# SIM7600G.net
KiCad netlist of a schematic drawn in Altium Designer
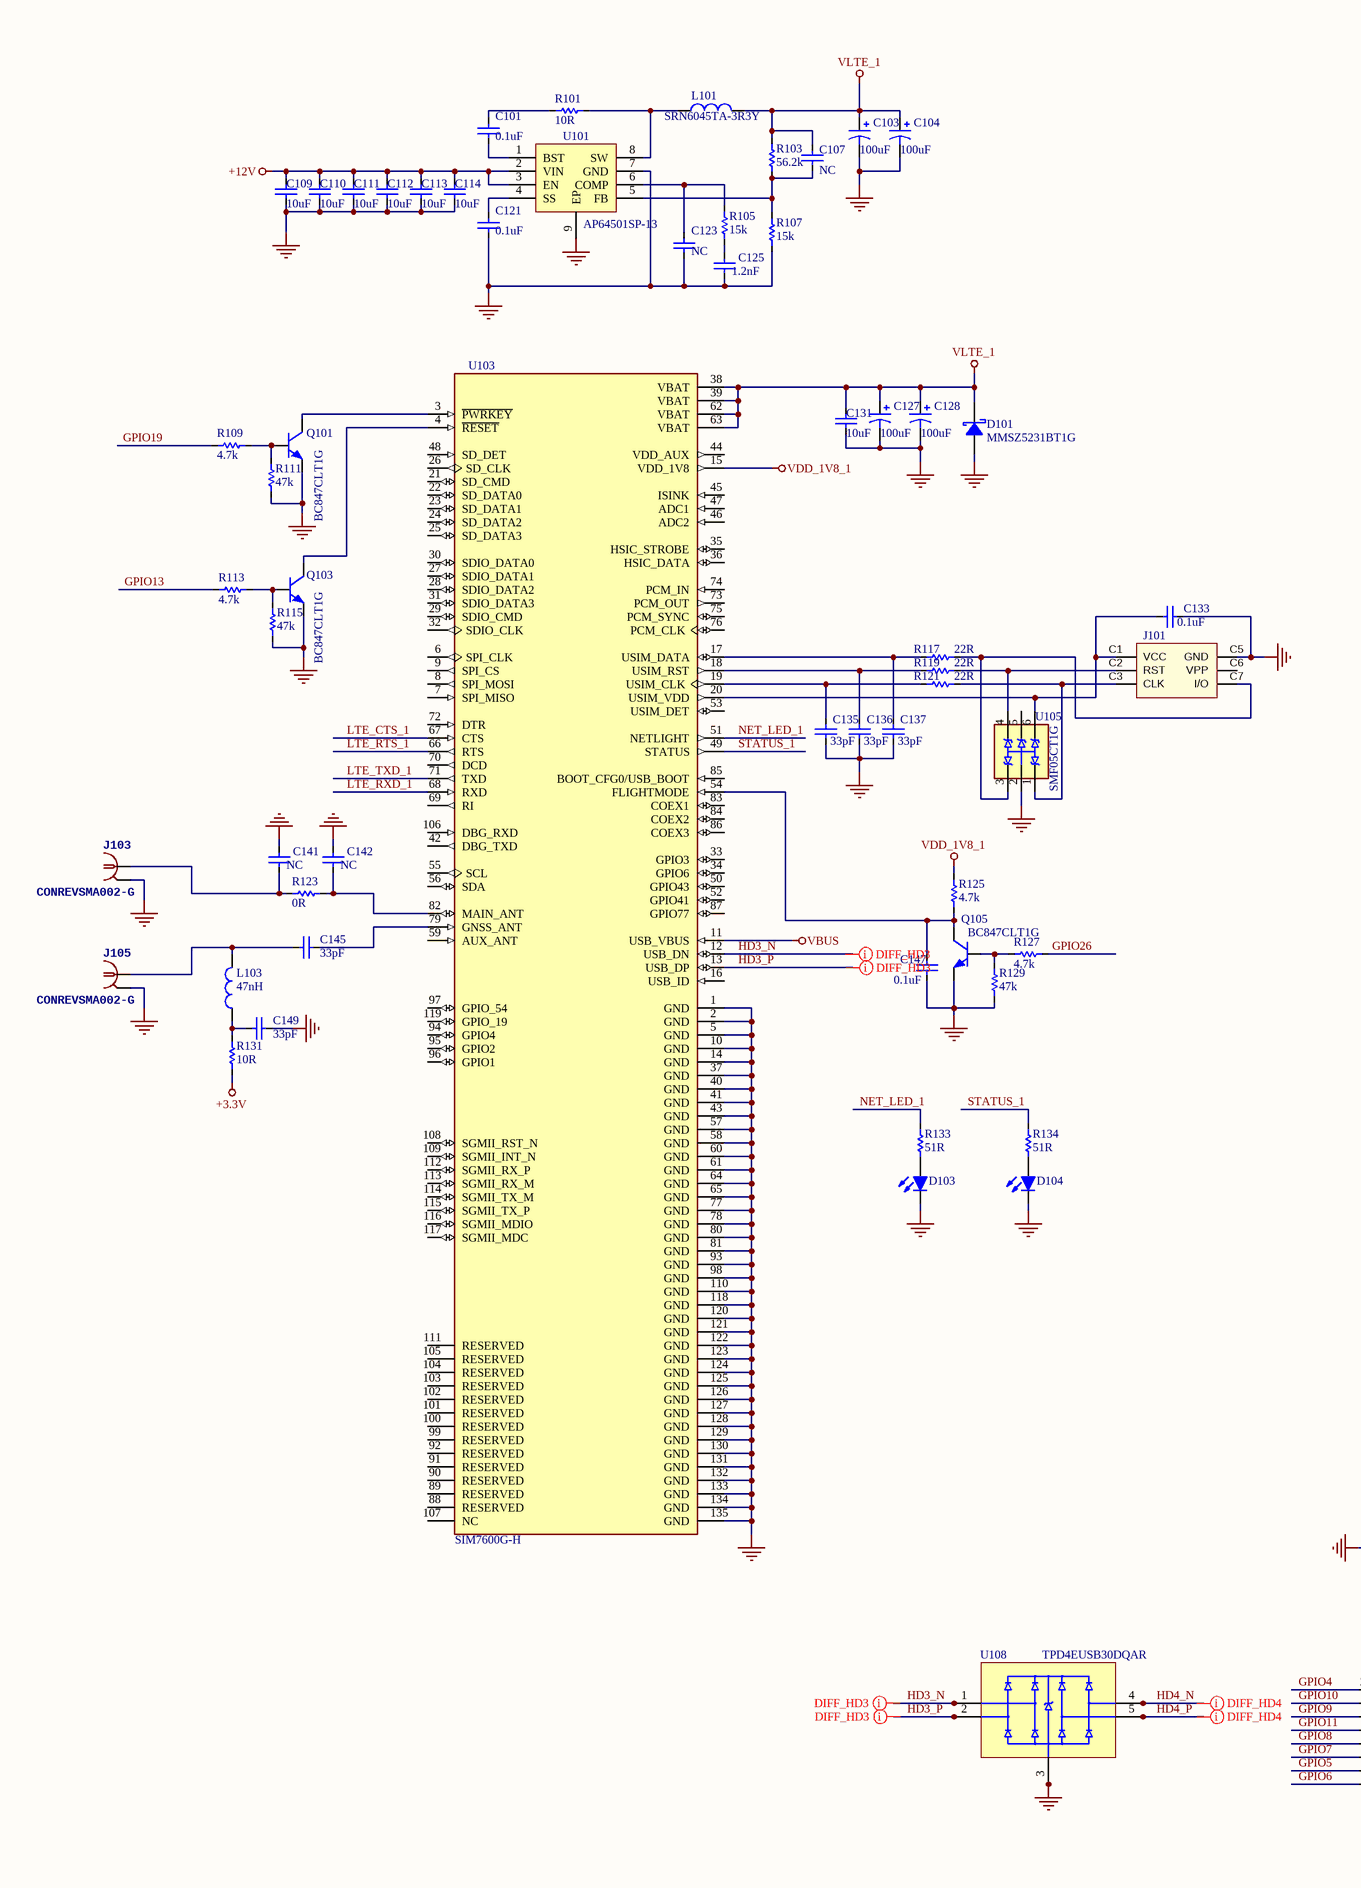
[diagram p0: SIM7600G.SchDoc, left]
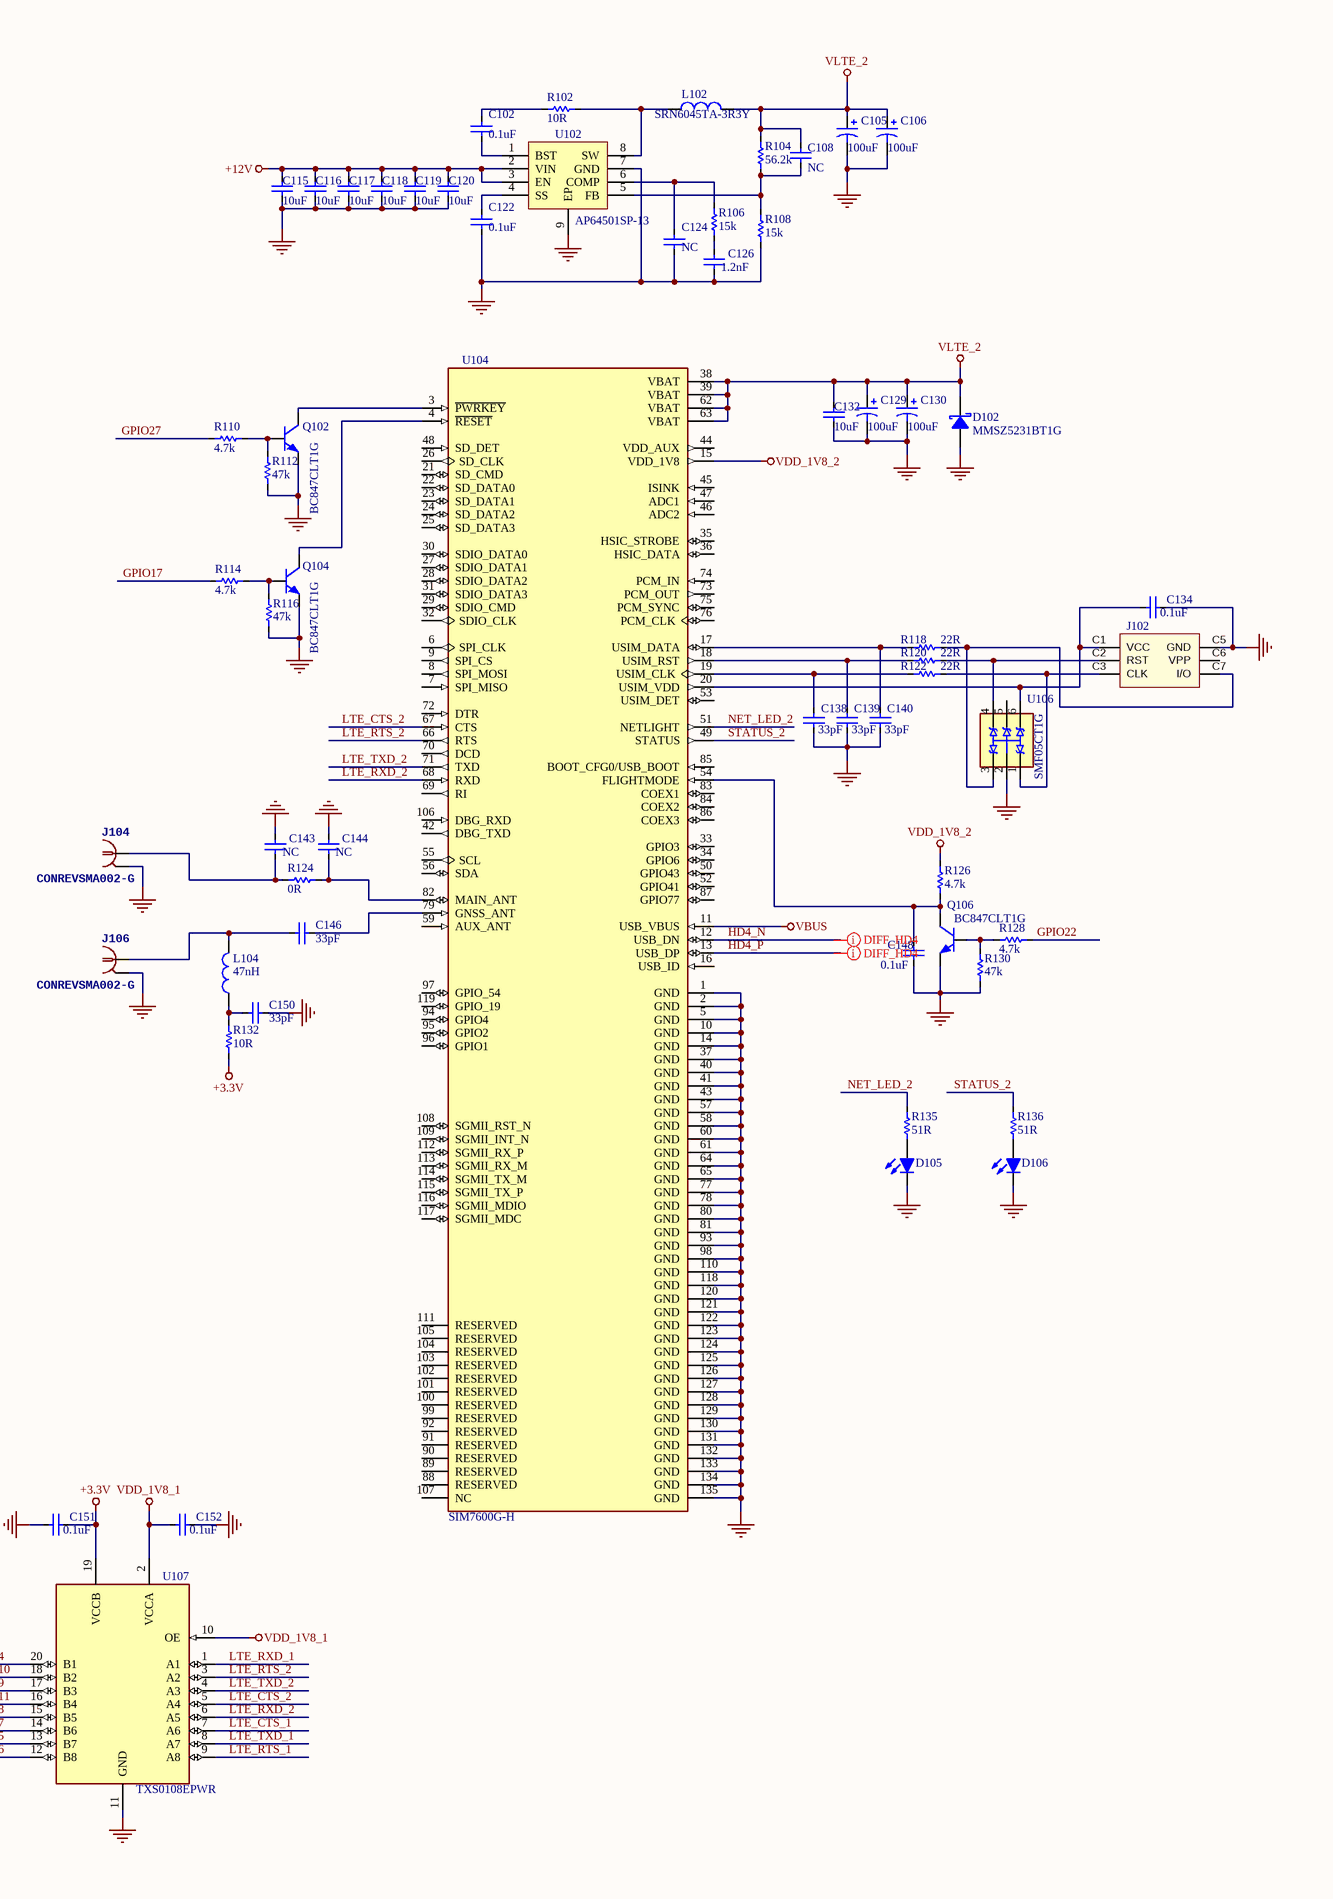
[diagram p1: SIM7600G.SchDoc, right]

(export (version "E")
  (design (tool "Eeschema 10.0.6"))
  (components
    (comp (ref "C101")
      (value "0.1uF")
      (footprint "C_0402_1005Metric")
      (description "0.1µF ±10% 50V")
      (fields
        (field (name "MANUFACTURER") "Yageo")
        (field (name "MANUFACTURER PART NUMBER") "CC0402KRX5R9BB104")
      )
      (libsource (lib "Miscellaneous Devices") (part "Cap"))
    )
    (comp (ref "C102")
      (value "0.1uF")
      (footprint "C_0402_1005Metric")
      (description "0.1µF ±10% 50V")
      (fields
        (field (name "MANUFACTURER") "Yageo")
        (field (name "MANUFACTURER PART NUMBER") "CC0402KRX5R9BB104")
      )
      (libsource (lib "Miscellaneous Devices") (part "Cap"))
    )
    (comp (ref "C103")
      (value "100uF")
      (footprint "CP_EIA-7343-31_Kemet-D")
      (description "CAP TANT 100UF 20% 10V 2917")
      (fields
        (field (name "MANUFACTURER PART NUMBER") "TAJD107M010RNJ")
        (field (name "MANUFACTURER") "AVX Corporation")
      )
      (libsource (lib "Miscellaneous Devices") (part "Cap Pol1"))
    )
    (comp (ref "C104")
      (value "100uF")
      (footprint "CP_EIA-7343-31_Kemet-D")
      (description "CAP TANT 100UF 20% 10V 2917")
      (fields
        (field (name "MANUFACTURER PART NUMBER") "TAJD107M010RNJ")
        (field (name "MANUFACTURER") "AVX Corporation")
      )
      (libsource (lib "Miscellaneous Devices") (part "Cap Pol1"))
    )
    (comp (ref "C105")
      (value "100uF")
      (footprint "CP_EIA-7343-31_Kemet-D")
      (description "CAP TANT 100UF 20% 10V 2917")
      (fields
        (field (name "MANUFACTURER PART NUMBER") "TAJD107M010RNJ")
        (field (name "MANUFACTURER") "AVX Corporation")
      )
      (libsource (lib "Miscellaneous Devices") (part "Cap Pol1"))
    )
    (comp (ref "C106")
      (value "100uF")
      (footprint "CP_EIA-7343-31_Kemet-D")
      (description "CAP TANT 100UF 20% 10V 2917")
      (fields
        (field (name "MANUFACTURER PART NUMBER") "TAJD107M010RNJ")
        (field (name "MANUFACTURER") "AVX Corporation")
      )
      (libsource (lib "Miscellaneous Devices") (part "Cap Pol1"))
    )
    (comp (ref "C107")
      (value "NC")
      (footprint "C_0402_1005Metric")
      (libsource (lib "Miscellaneous Devices") (part "Cap"))
    )
    (comp (ref "C108")
      (value "NC")
      (footprint "C_0402_1005Metric")
      (libsource (lib "Miscellaneous Devices") (part "Cap"))
    )
    (comp (ref "C109")
      (value "10uF")
      (footprint "C_0805_2012Metric")
      (description "10µF ±10% 35V")
      (fields
        (field (name "MANUFACTURER") "Murata")
        (field (name "MANUFACTURER PART NUMBER") "GRM21BR6YA106KE43L")
      )
      (libsource (lib "Miscellaneous Devices") (part "Cap"))
    )
    (comp (ref "C110")
      (value "10uF")
      (footprint "C_0805_2012Metric")
      (description "10µF ±10% 35V")
      (fields
        (field (name "MANUFACTURER") "Murata")
        (field (name "MANUFACTURER PART NUMBER") "GRM21BR6YA106KE43L")
      )
      (libsource (lib "Miscellaneous Devices") (part "Cap"))
    )
    (comp (ref "C111")
      (value "10uF")
      (footprint "C_0805_2012Metric")
      (description "10µF ±10% 35V")
      (fields
        (field (name "MANUFACTURER") "Murata")
        (field (name "MANUFACTURER PART NUMBER") "GRM21BR6YA106KE43L")
      )
      (libsource (lib "Miscellaneous Devices") (part "Cap"))
    )
    (comp (ref "C112")
      (value "10uF")
      (footprint "C_0805_2012Metric")
      (description "10µF ±10% 35V")
      (fields
        (field (name "MANUFACTURER") "Murata")
        (field (name "MANUFACTURER PART NUMBER") "GRM21BR6YA106KE43L")
      )
      (libsource (lib "Miscellaneous Devices") (part "Cap"))
    )
    (comp (ref "C113")
      (value "10uF")
      (footprint "C_0805_2012Metric")
      (description "10µF ±10% 35V")
      (fields
        (field (name "MANUFACTURER") "Murata")
        (field (name "MANUFACTURER PART NUMBER") "GRM21BR6YA106KE43L")
      )
      (libsource (lib "Miscellaneous Devices") (part "Cap"))
    )
    (comp (ref "C114")
      (value "10uF")
      (footprint "C_0805_2012Metric")
      (description "10µF ±10% 35V")
      (fields
        (field (name "MANUFACTURER") "Murata")
        (field (name "MANUFACTURER PART NUMBER") "GRM21BR6YA106KE43L")
      )
      (libsource (lib "Miscellaneous Devices") (part "Cap"))
    )
    (comp (ref "C115")
      (value "10uF")
      (footprint "C_0805_2012Metric")
      (description "10µF ±10% 35V")
      (fields
        (field (name "MANUFACTURER") "Murata")
        (field (name "MANUFACTURER PART NUMBER") "GRM21BR6YA106KE43L")
      )
      (libsource (lib "Miscellaneous Devices") (part "Cap"))
    )
    (comp (ref "C116")
      (value "10uF")
      (footprint "C_0805_2012Metric")
      (description "10µF ±10% 35V")
      (fields
        (field (name "MANUFACTURER") "Murata")
        (field (name "MANUFACTURER PART NUMBER") "GRM21BR6YA106KE43L")
      )
      (libsource (lib "Miscellaneous Devices") (part "Cap"))
    )
    (comp (ref "C117")
      (value "10uF")
      (footprint "C_0805_2012Metric")
      (description "10µF ±10% 35V")
      (fields
        (field (name "MANUFACTURER") "Murata")
        (field (name "MANUFACTURER PART NUMBER") "GRM21BR6YA106KE43L")
      )
      (libsource (lib "Miscellaneous Devices") (part "Cap"))
    )
    (comp (ref "C118")
      (value "10uF")
      (footprint "C_0805_2012Metric")
      (description "10µF ±10% 35V")
      (fields
        (field (name "MANUFACTURER") "Murata")
        (field (name "MANUFACTURER PART NUMBER") "GRM21BR6YA106KE43L")
      )
      (libsource (lib "Miscellaneous Devices") (part "Cap"))
    )
    (comp (ref "C119")
      (value "10uF")
      (footprint "C_0805_2012Metric")
      (description "10µF ±10% 35V")
      (fields
        (field (name "MANUFACTURER") "Murata")
        (field (name "MANUFACTURER PART NUMBER") "GRM21BR6YA106KE43L")
      )
      (libsource (lib "Miscellaneous Devices") (part "Cap"))
    )
    (comp (ref "C120")
      (value "10uF")
      (footprint "C_0805_2012Metric")
      (description "10µF ±10% 35V")
      (fields
        (field (name "MANUFACTURER") "Murata")
        (field (name "MANUFACTURER PART NUMBER") "GRM21BR6YA106KE43L")
      )
      (libsource (lib "Miscellaneous Devices") (part "Cap"))
    )
    (comp (ref "C121")
      (value "0.1uF")
      (footprint "C_0402_1005Metric")
      (description "0.1µF ±10% 50V")
      (fields
        (field (name "MANUFACTURER") "Yageo")
        (field (name "MANUFACTURER PART NUMBER") "CC0402KRX5R9BB104")
      )
      (libsource (lib "Miscellaneous Devices") (part "Cap"))
    )
    (comp (ref "C122")
      (value "0.1uF")
      (footprint "C_0402_1005Metric")
      (description "0.1µF ±10% 50V")
      (fields
        (field (name "MANUFACTURER") "Yageo")
        (field (name "MANUFACTURER PART NUMBER") "CC0402KRX5R9BB104")
      )
      (libsource (lib "Miscellaneous Devices") (part "Cap"))
    )
    (comp (ref "C123")
      (value "NC")
      (footprint "C_0402_1005Metric")
      (libsource (lib "Miscellaneous Devices") (part "Cap"))
    )
    (comp (ref "C124")
      (value "NC")
      (footprint "C_0402_1005Metric")
      (libsource (lib "Miscellaneous Devices") (part "Cap"))
    )
    (comp (ref "C125")
      (value "1.2nF")
      (footprint "C_0402_1005Metric")
      (description "1200pF ±10% 50V")
      (fields
        (field (name "MANUFACTURER") "Yageo")
        (field (name "MANUFACTURER PART NUMBER") "GRM155R71H122KA01J")
      )
      (libsource (lib "Miscellaneous Devices") (part "Cap"))
    )
    (comp (ref "C126")
      (value "1.2nF")
      (footprint "C_0402_1005Metric")
      (description "1200pF ±10% 50V")
      (fields
        (field (name "MANUFACTURER") "Yageo")
        (field (name "MANUFACTURER PART NUMBER") "GRM155R71H122KA01J")
      )
      (libsource (lib "Miscellaneous Devices") (part "Cap"))
    )
    (comp (ref "C127")
      (value "100uF")
      (footprint "CP_EIA-7343-31_Kemet-D")
      (description "CAP TANT 100UF 20% 10V 2917")
      (fields
        (field (name "MANUFACTURER PART NUMBER") "TAJD107M010RNJ")
        (field (name "MANUFACTURER") "AVX Corporation")
      )
      (libsource (lib "Miscellaneous Devices") (part "Cap Pol1"))
    )
    (comp (ref "C128")
      (value "100uF")
      (footprint "CP_EIA-7343-31_Kemet-D")
      (description "CAP TANT 100UF 20% 10V 2917")
      (fields
        (field (name "MANUFACTURER PART NUMBER") "TAJD107M010RNJ")
        (field (name "MANUFACTURER") "AVX Corporation")
      )
      (libsource (lib "Miscellaneous Devices") (part "Cap Pol1"))
    )
    (comp (ref "C129")
      (value "100uF")
      (footprint "CP_EIA-7343-31_Kemet-D")
      (description "CAP TANT 100UF 20% 10V 2917")
      (fields
        (field (name "MANUFACTURER PART NUMBER") "TAJD107M010RNJ")
        (field (name "MANUFACTURER") "AVX Corporation")
      )
      (libsource (lib "Miscellaneous Devices") (part "Cap Pol1"))
    )
    (comp (ref "C130")
      (value "100uF")
      (footprint "CP_EIA-7343-31_Kemet-D")
      (description "CAP TANT 100UF 20% 10V 2917")
      (fields
        (field (name "MANUFACTURER PART NUMBER") "TAJD107M010RNJ")
        (field (name "MANUFACTURER") "AVX Corporation")
      )
      (libsource (lib "Miscellaneous Devices") (part "Cap Pol1"))
    )
    (comp (ref "C131")
      (value "10uF")
      (footprint "C_0805_2012Metric")
      (description "10µF ±10% 35V")
      (fields
        (field (name "MANUFACTURER") "Murata")
        (field (name "MANUFACTURER PART NUMBER") "GRM21BR6YA106KE43L")
      )
      (libsource (lib "Miscellaneous Devices") (part "Cap"))
    )
    (comp (ref "C132")
      (value "10uF")
      (footprint "C_0805_2012Metric")
      (description "10µF ±10% 35V")
      (fields
        (field (name "MANUFACTURER") "Murata")
        (field (name "MANUFACTURER PART NUMBER") "GRM21BR6YA106KE43L")
      )
      (libsource (lib "Miscellaneous Devices") (part "Cap"))
    )
    (comp (ref "C133")
      (value "0.1uF")
      (footprint "C_0402_1005Metric")
      (description "0.1µF ±10% 50V")
      (fields
        (field (name "MANUFACTURER") "Yageo")
        (field (name "MANUFACTURER PART NUMBER") "CC0402KRX5R9BB104")
      )
      (libsource (lib "Miscellaneous Devices") (part "Cap"))
    )
    (comp (ref "C134")
      (value "0.1uF")
      (footprint "C_0402_1005Metric")
      (description "0.1µF ±10% 50V")
      (fields
        (field (name "MANUFACTURER") "Yageo")
        (field (name "MANUFACTURER PART NUMBER") "CC0402KRX5R9BB104")
      )
      (libsource (lib "Miscellaneous Devices") (part "Cap"))
    )
    (comp (ref "C135")
      (value "33pF")
      (footprint "C_0402_1005Metric")
      (description "33pF ±1% 50V")
      (fields
        (field (name "MANUFACTURER") "Yageo")
        (field (name "MANUFACTURER PART NUMBER") "CC0402FRNPO9BN330")
      )
      (libsource (lib "Miscellaneous Devices") (part "Cap"))
    )
    (comp (ref "C136")
      (value "33pF")
      (footprint "C_0402_1005Metric")
      (description "33pF ±1% 50V")
      (fields
        (field (name "MANUFACTURER") "Yageo")
        (field (name "MANUFACTURER PART NUMBER") "CC0402FRNPO9BN330")
      )
      (libsource (lib "Miscellaneous Devices") (part "Cap"))
    )
    (comp (ref "C137")
      (value "33pF")
      (footprint "C_0402_1005Metric")
      (description "33pF ±1% 50V")
      (fields
        (field (name "MANUFACTURER") "Yageo")
        (field (name "MANUFACTURER PART NUMBER") "CC0402FRNPO9BN330")
      )
      (libsource (lib "Miscellaneous Devices") (part "Cap"))
    )
    (comp (ref "C138")
      (value "33pF")
      (footprint "C_0402_1005Metric")
      (description "33pF ±1% 50V")
      (fields
        (field (name "MANUFACTURER") "Yageo")
        (field (name "MANUFACTURER PART NUMBER") "CC0402FRNPO9BN330")
      )
      (libsource (lib "Miscellaneous Devices") (part "Cap"))
    )
    (comp (ref "C139")
      (value "33pF")
      (footprint "C_0402_1005Metric")
      (description "33pF ±1% 50V")
      (fields
        (field (name "MANUFACTURER") "Yageo")
        (field (name "MANUFACTURER PART NUMBER") "CC0402FRNPO9BN330")
      )
      (libsource (lib "Miscellaneous Devices") (part "Cap"))
    )
    (comp (ref "C140")
      (value "33pF")
      (footprint "C_0402_1005Metric")
      (description "33pF ±1% 50V")
      (fields
        (field (name "MANUFACTURER") "Yageo")
        (field (name "MANUFACTURER PART NUMBER") "CC0402FRNPO9BN330")
      )
      (libsource (lib "Miscellaneous Devices") (part "Cap"))
    )
    (comp (ref "C141")
      (value "NC")
      (footprint "C_0402_1005Metric")
      (libsource (lib "Miscellaneous Devices") (part "Cap"))
    )
    (comp (ref "C142")
      (value "NC")
      (footprint "C_0402_1005Metric")
      (libsource (lib "Miscellaneous Devices") (part "Cap"))
    )
    (comp (ref "C143")
      (value "NC")
      (footprint "C_0402_1005Metric")
      (libsource (lib "Miscellaneous Devices") (part "Cap"))
    )
    (comp (ref "C144")
      (value "NC")
      (footprint "C_0402_1005Metric")
      (libsource (lib "Miscellaneous Devices") (part "Cap"))
    )
    (comp (ref "C145")
      (value "33pF")
      (footprint "C_0402_1005Metric")
      (description "33pF ±1% 50V")
      (fields
        (field (name "MANUFACTURER") "Yageo")
        (field (name "MANUFACTURER PART NUMBER") "CC0402FRNPO9BN330")
      )
      (libsource (lib "Miscellaneous Devices") (part "Cap"))
    )
    (comp (ref "C146")
      (value "33pF")
      (footprint "C_0402_1005Metric")
      (description "33pF ±1% 50V")
      (fields
        (field (name "MANUFACTURER") "Yageo")
        (field (name "MANUFACTURER PART NUMBER") "CC0402FRNPO9BN330")
      )
      (libsource (lib "Miscellaneous Devices") (part "Cap"))
    )
    (comp (ref "C147")
      (value "0.1uF")
      (footprint "C_0402_1005Metric")
      (description "0.1µF ±10% 50V")
      (fields
        (field (name "MANUFACTURER") "Yageo")
        (field (name "MANUFACTURER PART NUMBER") "CC0402KRX5R9BB104")
      )
      (libsource (lib "Miscellaneous Devices") (part "Cap"))
    )
    (comp (ref "C148")
      (value "0.1uF")
      (footprint "C_0402_1005Metric")
      (description "0.1µF ±10% 50V")
      (fields
        (field (name "MANUFACTURER") "Yageo")
        (field (name "MANUFACTURER PART NUMBER") "CC0402KRX5R9BB104")
      )
      (libsource (lib "Miscellaneous Devices") (part "Cap"))
    )
    (comp (ref "C149")
      (value "33pF")
      (footprint "C_0402_1005Metric")
      (description "33pF ±1% 50V")
      (fields
        (field (name "MANUFACTURER") "Yageo")
        (field (name "MANUFACTURER PART NUMBER") "CC0402FRNPO9BN330")
      )
      (libsource (lib "Miscellaneous Devices") (part "Cap"))
    )
    (comp (ref "C150")
      (value "33pF")
      (footprint "C_0402_1005Metric")
      (description "33pF ±1% 50V")
      (fields
        (field (name "MANUFACTURER") "Yageo")
        (field (name "MANUFACTURER PART NUMBER") "CC0402FRNPO9BN330")
      )
      (libsource (lib "Miscellaneous Devices") (part "Cap"))
    )
    (comp (ref "C151")
      (value "0.1uF")
      (footprint "C_0402_1005Metric")
      (description "0.1µF ±10% 50V")
      (fields
        (field (name "MANUFACTURER") "Yageo")
        (field (name "MANUFACTURER PART NUMBER") "CC0402KRX5R9BB104")
      )
      (libsource (lib "Miscellaneous Devices") (part "Cap"))
    )
    (comp (ref "C152")
      (value "0.1uF")
      (footprint "C_0402_1005Metric")
      (description "0.1µF ±10% 50V")
      (fields
        (field (name "MANUFACTURER") "Yageo")
        (field (name "MANUFACTURER PART NUMBER") "CC0402KRX5R9BB104")
      )
      (libsource (lib "Miscellaneous Devices") (part "Cap"))
    )
    (comp (ref "D101")
      (value "MMSZ5231BT1G")
      (footprint "SOD-123")
      (description "DIODE ZENER 5.1V 500MW SOD123")
      (fields (field (name "MANUFACTURER") "ON Semiconductor"))
      (libsource (lib "WirelessCharger") (part "Diode 10TQ035"))
    )
    (comp (ref "D102")
      (value "MMSZ5231BT1G")
      (footprint "SOD-123")
      (description "DIODE ZENER 5.1V 500MW SOD123")
      (fields (field (name "MANUFACTURER") "ON Semiconductor"))
      (libsource (lib "WirelessCharger") (part "Diode 10TQ035"))
    )
    (comp (ref "D103")
      (value "SML-D12M8WT86")
      (footprint "LED_0603_1608Metric")
      (description "LED GREEN DIFFUSED 0603 SMD")
      (fields (field (name "MANUFACTURER") "Rohm Semiconductor"))
      (libsource (lib "WirelessCharger") (part "LED1"))
    )
    (comp (ref "D104")
      (value "SML-D12M8WT86")
      (footprint "LED_0603_1608Metric")
      (description "LED GREEN DIFFUSED 0603 SMD")
      (fields (field (name "MANUFACTURER") "Rohm Semiconductor"))
      (libsource (lib "WirelessCharger") (part "LED1"))
    )
    (comp (ref "D105")
      (value "SML-D12M8WT86")
      (footprint "LED_0603_1608Metric")
      (description "LED GREEN DIFFUSED 0603 SMD")
      (fields (field (name "MANUFACTURER") "Rohm Semiconductor"))
      (libsource (lib "WirelessCharger") (part "LED1"))
    )
    (comp (ref "D106")
      (value "SML-D12M8WT86")
      (footprint "LED_0603_1608Metric")
      (description "LED GREEN DIFFUSED 0603 SMD")
      (fields (field (name "MANUFACTURER") "Rohm Semiconductor"))
      (libsource (lib "WirelessCharger") (part "LED1"))
    )
    (comp (ref "J101")
      (value "78646-3001")
      (footprint "78646-3001")
      (description "CONN MICRO SIM CARD PUSH-PULL")
      (fields (field (name "MANUFACTURER") "Molex"))
      (libsource (lib "WirelessCharger") (part "CN SimCard_63"))
    )
    (comp (ref "J102")
      (value "78646-3001")
      (footprint "78646-3001")
      (description "CONN MICRO SIM CARD PUSH-PULL")
      (fields (field (name "MANUFACTURER") "Molex"))
      (libsource (lib "WirelessCharger") (part "CN SimCard_63"))
    )
    (comp (ref "J103")
      (value "CONREVSMA002-G")
      (footprint "LINX_CONREVSMA002-G")
      (description "CONN SMA JACK STR EDGE MNT")
      (fields (field (name "MANUFACTURER") "Linx Technologies Inc."))
      (libsource (lib "axsem_connectors_v1-5") (part "SMA-SMD"))
    )
    (comp (ref "J104")
      (value "CONREVSMA002-G")
      (footprint "LINX_CONREVSMA002-G")
      (description "CONN SMA JACK STR EDGE MNT")
      (fields (field (name "MANUFACTURER") "Linx Technologies Inc."))
      (libsource (lib "axsem_connectors_v1-5") (part "SMA-SMD"))
    )
    (comp (ref "J105")
      (value "CONREVSMA002-G")
      (footprint "LINX_CONREVSMA002-G")
      (description "CONN SMA JACK STR EDGE MNT")
      (fields (field (name "MANUFACTURER") "Linx Technologies Inc."))
      (libsource (lib "axsem_connectors_v1-5") (part "SMA-SMD"))
    )
    (comp (ref "J106")
      (value "CONREVSMA002-G")
      (footprint "LINX_CONREVSMA002-G")
      (description "CONN SMA JACK STR EDGE MNT")
      (fields (field (name "MANUFACTURER") "Linx Technologies Inc."))
      (libsource (lib "axsem_connectors_v1-5") (part "SMA-SMD"))
    )
    (comp (ref "L101")
      (value "SRN6045TA-3R3Y")
      (footprint "L_Bourns_SRN6045TA")
      (description "FIXED IND 3.3UH 5A 21 MOHM SMD")
      (fields (field (name "MANUFACTURER") "Bourns Inc."))
      (libsource (lib "WirelessCharger") (part "Inductor"))
    )
    (comp (ref "L102")
      (value "SRN6045TA-3R3Y")
      (footprint "L_Bourns_SRN6045TA")
      (description "FIXED IND 3.3UH 5A 21 MOHM SMD")
      (fields (field (name "MANUFACTURER") "Bourns Inc."))
      (libsource (lib "WirelessCharger") (part "Inductor"))
    )
    (comp (ref "L103")
      (value "47nH")
      (footprint "SMD_R(0402)")
      (description "FIXED IND 47NH 210MA 1.08 OHM")
      (fields
        (field (name "MANUFACTURER PART NUMBER") "LQW15AN47NJ00D")
        (field (name "MANUFACTURER") "Murata")
      )
      (libsource (lib "WirelessCharger") (part "Inductor"))
    )
    (comp (ref "L104")
      (value "47nH")
      (footprint "SMD_R(0402)")
      (description "FIXED IND 47NH 210MA 1.08 OHM")
      (fields
        (field (name "MANUFACTURER PART NUMBER") "LQW15AN47NJ00D")
        (field (name "MANUFACTURER") "Murata")
      )
      (libsource (lib "WirelessCharger") (part "Inductor"))
    )
    (comp (ref "Q101")
      (value "BC847CLT1G")
      (footprint "SOT23-3")
      (description "TRANS NPN 45V 100MA SOT23-3")
      (fields (field (name "MANUFACTURER") "ON Semiconductor"))
      (libsource (lib "Wemo_Board") (part "2N3904"))
    )
    (comp (ref "Q102")
      (value "BC847CLT1G")
      (footprint "SOT23-3")
      (description "TRANS NPN 45V 100MA SOT23-3")
      (fields (field (name "MANUFACTURER") "ON Semiconductor"))
      (libsource (lib "Wemo_Board") (part "2N3904"))
    )
    (comp (ref "Q103")
      (value "BC847CLT1G")
      (footprint "SOT23-3")
      (description "TRANS NPN 45V 100MA SOT23-3")
      (fields (field (name "MANUFACTURER") "ON Semiconductor"))
      (libsource (lib "Wemo_Board") (part "2N3904"))
    )
    (comp (ref "Q104")
      (value "BC847CLT1G")
      (footprint "SOT23-3")
      (description "TRANS NPN 45V 100MA SOT23-3")
      (fields (field (name "MANUFACTURER") "ON Semiconductor"))
      (libsource (lib "Wemo_Board") (part "2N3904"))
    )
    (comp (ref "Q105")
      (value "BC847CLT1G")
      (footprint "SOT23-3")
      (description "TRANS NPN 45V 100MA SOT23-3")
      (fields (field (name "MANUFACTURER") "ON Semiconductor"))
      (libsource (lib "Wemo_Board") (part "2N3904"))
    )
    (comp (ref "Q106")
      (value "BC847CLT1G")
      (footprint "SOT23-3")
      (description "TRANS NPN 45V 100MA SOT23-3")
      (fields (field (name "MANUFACTURER") "ON Semiconductor"))
      (libsource (lib "Wemo_Board") (part "2N3904"))
    )
    (comp (ref "R101")
      (value "10R")
      (footprint "R_0402_1005Metric")
      (description "10 Ohms ±1% 0.063W")
      (fields
        (field (name "MANUFACTURER") "Yageo")
        (field (name "MANUFACTURER PART NUMBER") "RC0402FR-0710RL")
      )
      (libsource (lib "Miscellaneous Devices") (part "Res Semi"))
    )
    (comp (ref "R102")
      (value "10R")
      (footprint "R_0402_1005Metric")
      (description "10 Ohms ±1% 0.063W")
      (fields
        (field (name "MANUFACTURER") "Yageo")
        (field (name "MANUFACTURER PART NUMBER") "RC0402FR-0710RL")
      )
      (libsource (lib "Miscellaneous Devices") (part "Res Semi"))
    )
    (comp (ref "R103")
      (value "56.2k")
      (footprint "R_0402_1005Metric")
      (description "56.2 kOhms ±1% 0.063W")
      (fields
        (field (name "MANUFACTURER") "Yageo")
        (field (name "MANUFACTURER PART NUMBER") "RC0402FR-0756K2L")
      )
      (libsource (lib "Miscellaneous Devices") (part "Res Semi"))
    )
    (comp (ref "R104")
      (value "56.2k")
      (footprint "R_0402_1005Metric")
      (description "56.2 kOhms ±1% 0.063W")
      (fields
        (field (name "MANUFACTURER") "Yageo")
        (field (name "MANUFACTURER PART NUMBER") "RC0402FR-0756K2L")
      )
      (libsource (lib "Miscellaneous Devices") (part "Res Semi"))
    )
    (comp (ref "R105")
      (value "15k")
      (footprint "R_0402_1005Metric")
      (description "15 kOhms ±1% 0.063W")
      (fields
        (field (name "MANUFACTURER") "Yageo")
        (field (name "MANUFACTURER PART NUMBER") "RC0402FR-0715KL")
      )
      (libsource (lib "Miscellaneous Devices") (part "Res Semi"))
    )
    (comp (ref "R106")
      (value "15k")
      (footprint "R_0402_1005Metric")
      (description "15 kOhms ±1% 0.063W")
      (fields
        (field (name "MANUFACTURER") "Yageo")
        (field (name "MANUFACTURER PART NUMBER") "RC0402FR-0715KL")
      )
      (libsource (lib "Miscellaneous Devices") (part "Res Semi"))
    )
    (comp (ref "R107")
      (value "15k")
      (footprint "R_0402_1005Metric")
      (description "15 kOhms ±1% 0.063W")
      (fields
        (field (name "MANUFACTURER") "Yageo")
        (field (name "MANUFACTURER PART NUMBER") "RC0402FR-0715KL")
      )
      (libsource (lib "Miscellaneous Devices") (part "Res Semi"))
    )
    (comp (ref "R108")
      (value "15k")
      (footprint "R_0402_1005Metric")
      (description "15 kOhms ±1% 0.063W")
      (fields
        (field (name "MANUFACTURER") "Yageo")
        (field (name "MANUFACTURER PART NUMBER") "RC0402FR-0715KL")
      )
      (libsource (lib "Miscellaneous Devices") (part "Res Semi"))
    )
    (comp (ref "R109")
      (value "4.7k")
      (footprint "R_0402_1005Metric")
      (description "4.7 kOhms ±1% 0.063W")
      (fields
        (field (name "MANUFACTURER") "Yageo")
        (field (name "MANUFACTURER PART NUMBER") "RC0402FR-074K7L")
      )
      (libsource (lib "Miscellaneous Devices") (part "Res Semi"))
    )
    (comp (ref "R110")
      (value "4.7k")
      (footprint "R_0402_1005Metric")
      (description "4.7 kOhms ±1% 0.063W")
      (fields
        (field (name "MANUFACTURER") "Yageo")
        (field (name "MANUFACTURER PART NUMBER") "RC0402FR-074K7L")
      )
      (libsource (lib "Miscellaneous Devices") (part "Res Semi"))
    )
    (comp (ref "R111")
      (value "47k")
      (footprint "R_0402_1005Metric")
      (description "47 kOhms ±1% 0.063W")
      (fields
        (field (name "MANUFACTURER") "Yageo")
        (field (name "MANUFACTURER PART NUMBER") "RC0402FR-0747KL")
      )
      (libsource (lib "Miscellaneous Devices") (part "Res Semi"))
    )
    (comp (ref "R112")
      (value "47k")
      (footprint "R_0402_1005Metric")
      (description "47 kOhms ±1% 0.063W")
      (fields
        (field (name "MANUFACTURER") "Yageo")
        (field (name "MANUFACTURER PART NUMBER") "RC0402FR-0747KL")
      )
      (libsource (lib "Miscellaneous Devices") (part "Res Semi"))
    )
    (comp (ref "R113")
      (value "4.7k")
      (footprint "R_0402_1005Metric")
      (description "4.7 kOhms ±1% 0.063W")
      (fields
        (field (name "MANUFACTURER") "Yageo")
        (field (name "MANUFACTURER PART NUMBER") "RC0402FR-074K7L")
      )
      (libsource (lib "Miscellaneous Devices") (part "Res Semi"))
    )
    (comp (ref "R114")
      (value "4.7k")
      (footprint "R_0402_1005Metric")
      (description "4.7 kOhms ±1% 0.063W")
      (fields
        (field (name "MANUFACTURER") "Yageo")
        (field (name "MANUFACTURER PART NUMBER") "RC0402FR-074K7L")
      )
      (libsource (lib "Miscellaneous Devices") (part "Res Semi"))
    )
    (comp (ref "R115")
      (value "47k")
      (footprint "R_0402_1005Metric")
      (description "47 kOhms ±1% 0.063W")
      (fields
        (field (name "MANUFACTURER") "Yageo")
        (field (name "MANUFACTURER PART NUMBER") "RC0402FR-0747KL")
      )
      (libsource (lib "Miscellaneous Devices") (part "Res Semi"))
    )
    (comp (ref "R116")
      (value "47k")
      (footprint "R_0402_1005Metric")
      (description "47 kOhms ±1% 0.063W")
      (fields
        (field (name "MANUFACTURER") "Yageo")
        (field (name "MANUFACTURER PART NUMBER") "RC0402FR-0747KL")
      )
      (libsource (lib "Miscellaneous Devices") (part "Res Semi"))
    )
    (comp (ref "R117")
      (value "22R")
      (footprint "R_0402_1005Metric")
      (description "22 Ohms ±1% 0.063W")
      (fields
        (field (name "MANUFACTURER") "Yageo")
        (field (name "MANUFACTURER PART NUMBER") "RC0402FR-0722RL")
      )
      (libsource (lib "Miscellaneous Devices") (part "Res Semi"))
    )
    (comp (ref "R118")
      (value "22R")
      (footprint "R_0402_1005Metric")
      (description "22 Ohms ±1% 0.063W")
      (fields
        (field (name "MANUFACTURER") "Yageo")
        (field (name "MANUFACTURER PART NUMBER") "RC0402FR-0722RL")
      )
      (libsource (lib "Miscellaneous Devices") (part "Res Semi"))
    )
    (comp (ref "R119")
      (value "22R")
      (footprint "R_0402_1005Metric")
      (description "22 Ohms ±1% 0.063W")
      (fields
        (field (name "MANUFACTURER") "Yageo")
        (field (name "MANUFACTURER PART NUMBER") "RC0402FR-0722RL")
      )
      (libsource (lib "Miscellaneous Devices") (part "Res Semi"))
    )
    (comp (ref "R120")
      (value "22R")
      (footprint "R_0402_1005Metric")
      (description "22 Ohms ±1% 0.063W")
      (fields
        (field (name "MANUFACTURER") "Yageo")
        (field (name "MANUFACTURER PART NUMBER") "RC0402FR-0722RL")
      )
      (libsource (lib "Miscellaneous Devices") (part "Res Semi"))
    )
    (comp (ref "R121")
      (value "22R")
      (footprint "R_0402_1005Metric")
      (description "22 Ohms ±1% 0.063W")
      (fields
        (field (name "MANUFACTURER") "Yageo")
        (field (name "MANUFACTURER PART NUMBER") "RC0402FR-0722RL")
      )
      (libsource (lib "Miscellaneous Devices") (part "Res Semi"))
    )
    (comp (ref "R122")
      (value "22R")
      (footprint "R_0402_1005Metric")
      (description "22 Ohms ±1% 0.063W")
      (fields
        (field (name "MANUFACTURER") "Yageo")
        (field (name "MANUFACTURER PART NUMBER") "RC0402FR-0722RL")
      )
      (libsource (lib "Miscellaneous Devices") (part "Res Semi"))
    )
    (comp (ref "R123")
      (value "0R")
      (footprint "R_0402_1005Metric")
      (description "0 Ohms Jumper 0.063W")
      (fields
        (field (name "MANUFACTURER") "Yageo")
        (field (name "MANUFACTURER PART NUMBER") "RC0402FR-070RL")
      )
      (libsource (lib "Miscellaneous Devices") (part "Res Semi"))
    )
    (comp (ref "R124")
      (value "0R")
      (footprint "R_0402_1005Metric")
      (description "0 Ohms Jumper 0.063W")
      (fields
        (field (name "MANUFACTURER") "Yageo")
        (field (name "MANUFACTURER PART NUMBER") "RC0402FR-070RL")
      )
      (libsource (lib "Miscellaneous Devices") (part "Res Semi"))
    )
    (comp (ref "R125")
      (value "4.7k")
      (footprint "R_0402_1005Metric")
      (description "4.7 kOhms ±1% 0.063W")
      (fields
        (field (name "MANUFACTURER") "Yageo")
        (field (name "MANUFACTURER PART NUMBER") "RC0402FR-074K7L")
      )
      (libsource (lib "Miscellaneous Devices") (part "Res Semi"))
    )
    (comp (ref "R126")
      (value "4.7k")
      (footprint "R_0402_1005Metric")
      (description "4.7 kOhms ±1% 0.063W")
      (fields
        (field (name "MANUFACTURER") "Yageo")
        (field (name "MANUFACTURER PART NUMBER") "RC0402FR-074K7L")
      )
      (libsource (lib "Miscellaneous Devices") (part "Res Semi"))
    )
    (comp (ref "R127")
      (value "4.7k")
      (footprint "R_0402_1005Metric")
      (description "4.7 kOhms ±1% 0.063W")
      (fields
        (field (name "MANUFACTURER") "Yageo")
        (field (name "MANUFACTURER PART NUMBER") "RC0402FR-074K7L")
      )
      (libsource (lib "Miscellaneous Devices") (part "Res Semi"))
    )
    (comp (ref "R128")
      (value "4.7k")
      (footprint "R_0402_1005Metric")
      (description "4.7 kOhms ±1% 0.063W")
      (fields
        (field (name "MANUFACTURER") "Yageo")
        (field (name "MANUFACTURER PART NUMBER") "RC0402FR-074K7L")
      )
      (libsource (lib "Miscellaneous Devices") (part "Res Semi"))
    )
    (comp (ref "R129")
      (value "47k")
      (footprint "R_0402_1005Metric")
      (description "47 kOhms ±1% 0.063W")
      (fields
        (field (name "MANUFACTURER") "Yageo")
        (field (name "MANUFACTURER PART NUMBER") "RC0402FR-0747KL")
      )
      (libsource (lib "Miscellaneous Devices") (part "Res Semi"))
    )
    (comp (ref "R130")
      (value "47k")
      (footprint "R_0402_1005Metric")
      (description "47 kOhms ±1% 0.063W")
      (fields
        (field (name "MANUFACTURER") "Yageo")
        (field (name "MANUFACTURER PART NUMBER") "RC0402FR-0747KL")
      )
      (libsource (lib "Miscellaneous Devices") (part "Res Semi"))
    )
    (comp (ref "R131")
      (value "10R")
      (footprint "R_0402_1005Metric")
      (description "10 Ohms ±1% 0.063W")
      (fields
        (field (name "MANUFACTURER") "Yageo")
        (field (name "MANUFACTURER PART NUMBER") "RC0402FR-0710RL")
      )
      (libsource (lib "Miscellaneous Devices") (part "Res Semi"))
    )
    (comp (ref "R132")
      (value "10R")
      (footprint "R_0402_1005Metric")
      (description "10 Ohms ±1% 0.063W")
      (fields
        (field (name "MANUFACTURER") "Yageo")
        (field (name "MANUFACTURER PART NUMBER") "RC0402FR-0710RL")
      )
      (libsource (lib "Miscellaneous Devices") (part "Res Semi"))
    )
    (comp (ref "R133")
      (value "51R")
      (footprint "R_0402_1005Metric")
      (description "51 Ohms ±1% 0.063W")
      (fields
        (field (name "MANUFACTURER") "Yageo")
        (field (name "MANUFACTURER PART NUMBER") "RC0402FR-0751RL")
      )
      (libsource (lib "Miscellaneous Devices") (part "Res Semi"))
    )
    (comp (ref "R134")
      (value "51R")
      (footprint "R_0402_1005Metric")
      (description "51 Ohms ±1% 0.063W")
      (fields
        (field (name "MANUFACTURER") "Yageo")
        (field (name "MANUFACTURER PART NUMBER") "RC0402FR-0751RL")
      )
      (libsource (lib "Miscellaneous Devices") (part "Res Semi"))
    )
    (comp (ref "R135")
      (value "51R")
      (footprint "R_0402_1005Metric")
      (description "51 Ohms ±1% 0.063W")
      (fields
        (field (name "MANUFACTURER") "Yageo")
        (field (name "MANUFACTURER PART NUMBER") "RC0402FR-0751RL")
      )
      (libsource (lib "Miscellaneous Devices") (part "Res Semi"))
    )
    (comp (ref "R136")
      (value "51R")
      (footprint "R_0402_1005Metric")
      (description "51 Ohms ±1% 0.063W")
      (fields
        (field (name "MANUFACTURER") "Yageo")
        (field (name "MANUFACTURER PART NUMBER") "RC0402FR-0751RL")
      )
      (libsource (lib "Miscellaneous Devices") (part "Res Semi"))
    )
    (comp (ref "U101")
      (value "AP64501SP-13")
      (footprint "SOIC-8-1EP_3.9x4.9mm_P1.27mm_EP2.95x4.9mm_Mask2.71x3.4mm_ThermalVias")
      (description "DCDC CONV HV BUCK SO-8EP")
      (fields (field (name "MANUFACTURER") "Diodes Incorporated"))
      (libsource (lib "WirelessCharger") (part "AP64501SP-13"))
    )
    (comp (ref "U102")
      (value "AP64501SP-13")
      (footprint "SOIC-8-1EP_3.9x4.9mm_P1.27mm_EP2.95x4.9mm_Mask2.71x3.4mm_ThermalVias")
      (description "DCDC CONV HV BUCK SO-8EP")
      (fields (field (name "MANUFACTURER") "Diodes Incorporated"))
      (libsource (lib "WirelessCharger") (part "AP64501SP-13"))
    )
    (comp (ref "U103")
      (value "SIM7600G-H")
      (footprint "IC_SIM7600G")
      (description "LTE Cat-4 Module")
      (fields (field (name "MANUFACTURER") "Simcom"))
      (libsource (lib "WirelessCharger") (part "SIM7600G"))
    )
    (comp (ref "U104")
      (value "SIM7600G-H")
      (footprint "IC_SIM7600G")
      (description "LTE Cat-4 Module")
      (fields (field (name "MANUFACTURER") "Simcom"))
      (libsource (lib "WirelessCharger") (part "SIM7600G"))
    )
    (comp (ref "U105")
      (value "SMF05CT1G")
      (footprint "SOT-363")
      (description "TRANS VOLTAGE SUPPRESSOR DIODE,")
      (fields (field (name "MANUFACTURER") "ON Semiconductor"))
      (libsource (lib "SnapEDAsch") (part "SMF05CT1G"))
    )
    (comp (ref "U106")
      (value "SMF05CT1G")
      (footprint "SOT-363")
      (description "TRANS VOLTAGE SUPPRESSOR DIODE,")
      (fields (field (name "MANUFACTURER") "ON Semiconductor"))
      (libsource (lib "SnapEDAsch") (part "SMF05CT1G"))
    )
    (comp (ref "U107")
      (value "TXS0108EPWR")
      (footprint "SOP65P640X120-20N")
      (description "8-Bit Bidirectional Voltage-Level Shifter For Open-Drain And Push-Pull Application")
      (fields (field (name "MANUFACTURER") "Texas Instruments"))
      (libsource (lib "EMDO901_LTE_GPS") (part "TXS0108EPWR"))
    )
    (comp (ref "U108")
      (value "TPD4EUSB30DQAR")
      (footprint "USON-10_2.5x1.0mm_P0.5mm")
      (description "TVS DIODE 5.5V 8V 10USON")
      (fields (field (name "MF") "Texas Instruments"))
      (libsource (lib "WirelessCharger") (part "TPD4EUSB30DQAR"))
    )
  )
  (nets
    (net (code "1") (name "+3.3V") (class "Default")
      (node (ref "C151") (pin "2") (pinfunction "2_2") (pintype "passive"))
      (node (ref "R131") (pin "1") (pinfunction "1_1") (pintype "passive"))
      (node (ref "R132") (pin "1") (pinfunction "1_1") (pintype "passive"))
      (node (ref "U107") (pin "19") (pinfunction "VCCB_19") (pintype "power_in"))
    )
    (net (code "2") (name "+12V") (class "Default")
      (node (ref "C109") (pin "1") (pinfunction "1_1") (pintype "passive"))
      (node (ref "C110") (pin "1") (pinfunction "1_1") (pintype "passive"))
      (node (ref "C111") (pin "1") (pinfunction "1_1") (pintype "passive"))
      (node (ref "C112") (pin "1") (pinfunction "1_1") (pintype "passive"))
      (node (ref "C113") (pin "1") (pinfunction "1_1") (pintype "passive"))
      (node (ref "C114") (pin "1") (pinfunction "1_1") (pintype "passive"))
      (node (ref "C115") (pin "1") (pinfunction "1_1") (pintype "passive"))
      (node (ref "C116") (pin "1") (pinfunction "1_1") (pintype "passive"))
      (node (ref "C117") (pin "1") (pinfunction "1_1") (pintype "passive"))
      (node (ref "C118") (pin "1") (pinfunction "1_1") (pintype "passive"))
      (node (ref "C119") (pin "1") (pinfunction "1_1") (pintype "passive"))
      (node (ref "C120") (pin "1") (pinfunction "1_1") (pintype "passive"))
      (node (ref "U101") (pin "2") (pinfunction "VIN_2") (pintype "passive"))
      (node (ref "U101") (pin "3") (pinfunction "EN_3") (pintype "passive"))
      (node (ref "U102") (pin "2") (pinfunction "VIN_2") (pintype "passive"))
      (node (ref "U102") (pin "3") (pinfunction "EN_3") (pintype "passive"))
    )
    (net (code "3") (name "/GPIO4") (class "Default")
      (node (ref "U107") (pin "20") (pinfunction "B1_20") (pintype "bidirectional"))
    )
    (net (code "4") (name "/GPIO5") (class "Default")
      (node (ref "U107") (pin "13") (pinfunction "B7_13") (pintype "bidirectional"))
    )
    (net (code "5") (name "/GPIO6") (class "Default")
      (node (ref "U107") (pin "12") (pinfunction "B8_12") (pintype "bidirectional"))
    )
    (net (code "6") (name "/GPIO7") (class "Default")
      (node (ref "U107") (pin "14") (pinfunction "B6_14") (pintype "bidirectional"))
    )
    (net (code "7") (name "/GPIO8") (class "Default")
      (node (ref "U107") (pin "15") (pinfunction "B5_15") (pintype "bidirectional"))
    )
    (net (code "8") (name "/GPIO9") (class "Default")
      (node (ref "U107") (pin "17") (pinfunction "B3_17") (pintype "bidirectional"))
    )
    (net (code "9") (name "/GPIO10") (class "Default")
      (node (ref "U107") (pin "18") (pinfunction "B2_18") (pintype "bidirectional"))
    )
    (net (code "10") (name "/GPIO11") (class "Default")
      (node (ref "U107") (pin "16") (pinfunction "B4_16") (pintype "bidirectional"))
    )
    (net (code "11") (name "/GPIO13") (class "Default")
      (node (ref "R113") (pin "2") (pinfunction "2_2") (pintype "passive"))
    )
    (net (code "12") (name "/GPIO17") (class "Default")
      (node (ref "R114") (pin "2") (pinfunction "2_2") (pintype "passive"))
    )
    (net (code "13") (name "/GPIO19") (class "Default")
      (node (ref "R109") (pin "2") (pinfunction "2_2") (pintype "passive"))
    )
    (net (code "14") (name "/GPIO22") (class "Default")
      (node (ref "R128") (pin "1") (pinfunction "1_1") (pintype "passive"))
    )
    (net (code "15") (name "/GPIO26") (class "Default")
      (node (ref "R127") (pin "1") (pinfunction "1_1") (pintype "passive"))
    )
    (net (code "16") (name "/GPIO27") (class "Default")
      (node (ref "R110") (pin "2") (pinfunction "2_2") (pintype "passive"))
    )
    (net (code "17") (name "/HD3_N") (class "Default")
      (node (ref "U103") (pin "12") (pinfunction "USB_DN_12") (pintype "bidirectional"))
      (node (ref "U108") (pin "1") (pinfunction "D1+_1") (pintype "passive"))
      (node (ref "U108") (pin "10") (pinfunction "NC_10_10") (pintype "passive"))
    )
    (net (code "18") (name "/HD3_P") (class "Default")
      (node (ref "U103") (pin "13") (pinfunction "USB_DP_13") (pintype "bidirectional"))
      (node (ref "U108") (pin "2") (pinfunction "D1-_2") (pintype "passive"))
      (node (ref "U108") (pin "9") (pinfunction "NC_9_9") (pintype "passive"))
    )
    (net (code "19") (name "/HD4_N") (class "Default")
      (node (ref "U104") (pin "12") (pinfunction "USB_DN_12") (pintype "bidirectional"))
      (node (ref "U108") (pin "4") (pinfunction "D2+_4") (pintype "passive"))
      (node (ref "U108") (pin "7") (pinfunction "NC_7_7") (pintype "passive"))
    )
    (net (code "20") (name "/HD4_P") (class "Default")
      (node (ref "U104") (pin "13") (pinfunction "USB_DP_13") (pintype "bidirectional"))
      (node (ref "U108") (pin "5") (pinfunction "D2-_5") (pintype "passive"))
      (node (ref "U108") (pin "6") (pinfunction "NC_6_6") (pintype "passive"))
    )
    (net (code "21") (name "/LTE_CTS_1") (class "Default")
      (node (ref "U103") (pin "67") (pinfunction "CTS_67") (pintype "input"))
      (node (ref "U107") (pin "7") (pinfunction "A6_7") (pintype "bidirectional"))
    )
    (net (code "22") (name "/LTE_CTS_2") (class "Default")
      (node (ref "U104") (pin "67") (pinfunction "CTS_67") (pintype "input"))
      (node (ref "U107") (pin "5") (pinfunction "A4_5") (pintype "bidirectional"))
    )
    (net (code "23") (name "/LTE_RTS_1") (class "Default")
      (node (ref "U103") (pin "66") (pinfunction "RTS_66") (pintype "output"))
      (node (ref "U107") (pin "9") (pinfunction "A8_9") (pintype "bidirectional"))
    )
    (net (code "24") (name "/LTE_RTS_2") (class "Default")
      (node (ref "U104") (pin "66") (pinfunction "RTS_66") (pintype "output"))
      (node (ref "U107") (pin "3") (pinfunction "A2_3") (pintype "bidirectional"))
    )
    (net (code "25") (name "/LTE_RXD_1") (class "Default")
      (node (ref "U103") (pin "68") (pinfunction "RXD_68") (pintype "input"))
      (node (ref "U107") (pin "1") (pinfunction "A1_1") (pintype "bidirectional"))
    )
    (net (code "26") (name "/LTE_RXD_2") (class "Default")
      (node (ref "U104") (pin "68") (pinfunction "RXD_68") (pintype "input"))
      (node (ref "U107") (pin "6") (pinfunction "A5_6") (pintype "bidirectional"))
    )
    (net (code "27") (name "/LTE_TXD_1") (class "Default")
      (node (ref "U103") (pin "71") (pinfunction "TXD_71") (pintype "output"))
      (node (ref "U107") (pin "8") (pinfunction "A7_8") (pintype "bidirectional"))
    )
    (net (code "28") (name "/LTE_TXD_2") (class "Default")
      (node (ref "U104") (pin "71") (pinfunction "TXD_71") (pintype "output"))
      (node (ref "U107") (pin "4") (pinfunction "A3_4") (pintype "bidirectional"))
    )
    (net (code "29") (name "/NET_LED_1") (class "Default")
      (node (ref "R133") (pin "1") (pinfunction "1_1") (pintype "passive"))
      (node (ref "U103") (pin "51") (pinfunction "NETLIGHT_51") (pintype "output"))
    )
    (net (code "30") (name "/NET_LED_2") (class "Default")
      (node (ref "R135") (pin "1") (pinfunction "1_1") (pintype "passive"))
      (node (ref "U104") (pin "51") (pinfunction "NETLIGHT_51") (pintype "output"))
    )
    (net (code "31") (name "/STATUS_1") (class "Default")
      (node (ref "R134") (pin "1") (pinfunction "1_1") (pintype "passive"))
      (node (ref "U103") (pin "49") (pinfunction "STATUS_49") (pintype "output"))
    )
    (net (code "32") (name "/STATUS_2") (class "Default")
      (node (ref "R136") (pin "1") (pinfunction "1_1") (pintype "passive"))
      (node (ref "U104") (pin "49") (pinfunction "STATUS_49") (pintype "output"))
    )
    (net (code "33") (name "GND") (class "Default")
      (node (ref "C103") (pin "2") (pinfunction "2_2") (pintype "passive"))
      (node (ref "C104") (pin "2") (pinfunction "2_2") (pintype "passive"))
      (node (ref "C105") (pin "2") (pinfunction "2_2") (pintype "passive"))
      (node (ref "C106") (pin "2") (pinfunction "2_2") (pintype "passive"))
      (node (ref "C109") (pin "2") (pinfunction "2_2") (pintype "passive"))
      (node (ref "C110") (pin "2") (pinfunction "2_2") (pintype "passive"))
      (node (ref "C111") (pin "2") (pinfunction "2_2") (pintype "passive"))
      (node (ref "C112") (pin "2") (pinfunction "2_2") (pintype "passive"))
      (node (ref "C113") (pin "2") (pinfunction "2_2") (pintype "passive"))
      (node (ref "C114") (pin "2") (pinfunction "2_2") (pintype "passive"))
      (node (ref "C115") (pin "2") (pinfunction "2_2") (pintype "passive"))
      (node (ref "C116") (pin "2") (pinfunction "2_2") (pintype "passive"))
      (node (ref "C117") (pin "2") (pinfunction "2_2") (pintype "passive"))
      (node (ref "C118") (pin "2") (pinfunction "2_2") (pintype "passive"))
      (node (ref "C119") (pin "2") (pinfunction "2_2") (pintype "passive"))
      (node (ref "C120") (pin "2") (pinfunction "2_2") (pintype "passive"))
      (node (ref "C121") (pin "2") (pinfunction "2_2") (pintype "passive"))
      (node (ref "C122") (pin "2") (pinfunction "2_2") (pintype "passive"))
      (node (ref "C123") (pin "2") (pinfunction "2_2") (pintype "passive"))
      (node (ref "C124") (pin "2") (pinfunction "2_2") (pintype "passive"))
      (node (ref "C125") (pin "2") (pinfunction "2_2") (pintype "passive"))
      (node (ref "C126") (pin "2") (pinfunction "2_2") (pintype "passive"))
      (node (ref "C127") (pin "2") (pinfunction "2_2") (pintype "passive"))
      (node (ref "C128") (pin "2") (pinfunction "2_2") (pintype "passive"))
      (node (ref "C129") (pin "2") (pinfunction "2_2") (pintype "passive"))
      (node (ref "C130") (pin "2") (pinfunction "2_2") (pintype "passive"))
      (node (ref "C131") (pin "2") (pinfunction "2_2") (pintype "passive"))
      (node (ref "C132") (pin "2") (pinfunction "2_2") (pintype "passive"))
      (node (ref "C133") (pin "2") (pinfunction "2_2") (pintype "passive"))
      (node (ref "C134") (pin "2") (pinfunction "2_2") (pintype "passive"))
      (node (ref "C135") (pin "1") (pinfunction "1_1") (pintype "passive"))
      (node (ref "C136") (pin "1") (pinfunction "1_1") (pintype "passive"))
      (node (ref "C137") (pin "1") (pinfunction "1_1") (pintype "passive"))
      (node (ref "C138") (pin "1") (pinfunction "1_1") (pintype "passive"))
      (node (ref "C139") (pin "1") (pinfunction "1_1") (pintype "passive"))
      (node (ref "C140") (pin "1") (pinfunction "1_1") (pintype "passive"))
      (node (ref "C141") (pin "1") (pinfunction "1_1") (pintype "passive"))
      (node (ref "C142") (pin "1") (pinfunction "1_1") (pintype "passive"))
      (node (ref "C143") (pin "1") (pinfunction "1_1") (pintype "passive"))
      (node (ref "C144") (pin "1") (pinfunction "1_1") (pintype "passive"))
      (node (ref "C147") (pin "1") (pinfunction "1_1") (pintype "passive"))
      (node (ref "C148") (pin "1") (pinfunction "1_1") (pintype "passive"))
      (node (ref "C149") (pin "1") (pinfunction "1_1") (pintype "passive"))
      (node (ref "C150") (pin "1") (pinfunction "1_1") (pintype "passive"))
      (node (ref "C151") (pin "1") (pinfunction "1_1") (pintype "passive"))
      (node (ref "C152") (pin "2") (pinfunction "2_2") (pintype "passive"))
      (node (ref "D101") (pin "A") (pinfunction "A_A") (pintype "passive"))
      (node (ref "D102") (pin "A") (pinfunction "A_A") (pintype "passive"))
      (node (ref "D103") (pin "1") (pinfunction "K_1") (pintype "passive"))
      (node (ref "D104") (pin "1") (pinfunction "K_1") (pintype "passive"))
      (node (ref "D105") (pin "1") (pinfunction "K_1") (pintype "passive"))
      (node (ref "D106") (pin "1") (pinfunction "K_1") (pintype "passive"))
      (node (ref "J101") (pin "C5") (pinfunction "GND_C5") (pintype "passive"))
      (node (ref "J102") (pin "C5") (pinfunction "GND_C5") (pintype "passive"))
      (node (ref "J103") (pin "2") (pinfunction "GND_2") (pintype "power_in"))
      (node (ref "J104") (pin "2") (pinfunction "GND_2") (pintype "power_in"))
      (node (ref "J105") (pin "2") (pinfunction "GND_2") (pintype "power_in"))
      (node (ref "J106") (pin "2") (pinfunction "GND_2") (pintype "power_in"))
      (node (ref "Q101") (pin "2") (pinfunction "E_2") (pintype "passive"))
      (node (ref "Q102") (pin "2") (pinfunction "E_2") (pintype "passive"))
      (node (ref "Q103") (pin "2") (pinfunction "E_2") (pintype "passive"))
      (node (ref "Q104") (pin "2") (pinfunction "E_2") (pintype "passive"))
      (node (ref "Q105") (pin "2") (pinfunction "E_2") (pintype "passive"))
      (node (ref "Q106") (pin "2") (pinfunction "E_2") (pintype "passive"))
      (node (ref "R107") (pin "2") (pinfunction "2_2") (pintype "passive"))
      (node (ref "R108") (pin "2") (pinfunction "2_2") (pintype "passive"))
      (node (ref "R111") (pin "1") (pinfunction "1_1") (pintype "passive"))
      (node (ref "R112") (pin "1") (pinfunction "1_1") (pintype "passive"))
      (node (ref "R115") (pin "1") (pinfunction "1_1") (pintype "passive"))
      (node (ref "R116") (pin "1") (pinfunction "1_1") (pintype "passive"))
      (node (ref "R129") (pin "1") (pinfunction "1_1") (pintype "passive"))
      (node (ref "R130") (pin "1") (pinfunction "1_1") (pintype "passive"))
      (node (ref "U101") (pin "7") (pinfunction "GND_7") (pintype "passive"))
      (node (ref "U101") (pin "9") (pinfunction "EP_9") (pintype "passive"))
      (node (ref "U102") (pin "7") (pinfunction "GND_7") (pintype "passive"))
      (node (ref "U102") (pin "9") (pinfunction "EP_9") (pintype "passive"))
      (node (ref "U103") (pin "1") (pinfunction "GND_1") (pintype "power_in"))
      (node (ref "U103") (pin "10") (pinfunction "GND_10") (pintype "power_in"))
      (node (ref "U103") (pin "110") (pinfunction "GND_110") (pintype "power_in"))
      (node (ref "U103") (pin "118") (pinfunction "GND_118") (pintype "power_in"))
      (node (ref "U103") (pin "120") (pinfunction "GND_120") (pintype "power_in"))
      (node (ref "U103") (pin "121") (pinfunction "GND_121") (pintype "power_in"))
      (node (ref "U103") (pin "122") (pinfunction "GND_122") (pintype "power_in"))
      (node (ref "U103") (pin "123") (pinfunction "GND_123") (pintype "power_in"))
      (node (ref "U103") (pin "124") (pinfunction "GND_124") (pintype "power_in"))
      (node (ref "U103") (pin "125") (pinfunction "GND_125") (pintype "power_in"))
      (node (ref "U103") (pin "126") (pinfunction "GND_126") (pintype "power_in"))
      (node (ref "U103") (pin "127") (pinfunction "GND_127") (pintype "power_in"))
      (node (ref "U103") (pin "128") (pinfunction "GND_128") (pintype "power_in"))
      (node (ref "U103") (pin "129") (pinfunction "GND_129") (pintype "power_in"))
      (node (ref "U103") (pin "130") (pinfunction "GND_130") (pintype "power_in"))
      (node (ref "U103") (pin "131") (pinfunction "GND_131") (pintype "power_in"))
      (node (ref "U103") (pin "132") (pinfunction "GND_132") (pintype "power_in"))
      (node (ref "U103") (pin "133") (pinfunction "GND_133") (pintype "power_in"))
      (node (ref "U103") (pin "134") (pinfunction "GND_134") (pintype "power_in"))
      (node (ref "U103") (pin "135") (pinfunction "GND_135") (pintype "power_in"))
      (node (ref "U103") (pin "14") (pinfunction "GND_14") (pintype "power_in"))
      (node (ref "U103") (pin "2") (pinfunction "GND_2") (pintype "power_in"))
      (node (ref "U103") (pin "37") (pinfunction "GND_37") (pintype "power_in"))
      (node (ref "U103") (pin "40") (pinfunction "GND_40") (pintype "power_in"))
      (node (ref "U103") (pin "41") (pinfunction "GND_41") (pintype "power_in"))
      (node (ref "U103") (pin "43") (pinfunction "GND_43") (pintype "power_in"))
      (node (ref "U103") (pin "5") (pinfunction "GND_5") (pintype "power_in"))
      (node (ref "U103") (pin "57") (pinfunction "GND_57") (pintype "power_in"))
      (node (ref "U103") (pin "58") (pinfunction "GND_58") (pintype "power_in"))
      (node (ref "U103") (pin "60") (pinfunction "GND_60") (pintype "power_in"))
      (node (ref "U103") (pin "61") (pinfunction "GND_61") (pintype "power_in"))
      (node (ref "U103") (pin "64") (pinfunction "GND_64") (pintype "power_in"))
      (node (ref "U103") (pin "65") (pinfunction "GND_65") (pintype "power_in"))
      (node (ref "U103") (pin "77") (pinfunction "GND_77") (pintype "power_in"))
      (node (ref "U103") (pin "78") (pinfunction "GND_78") (pintype "power_in"))
      (node (ref "U103") (pin "80") (pinfunction "GND_80") (pintype "power_in"))
      (node (ref "U103") (pin "81") (pinfunction "GND_81") (pintype "power_in"))
      (node (ref "U103") (pin "93") (pinfunction "GND_93") (pintype "power_in"))
      (node (ref "U103") (pin "98") (pinfunction "GND_98") (pintype "power_in"))
      (node (ref "U104") (pin "1") (pinfunction "GND_1") (pintype "power_in"))
      (node (ref "U104") (pin "10") (pinfunction "GND_10") (pintype "power_in"))
      (node (ref "U104") (pin "110") (pinfunction "GND_110") (pintype "power_in"))
      (node (ref "U104") (pin "118") (pinfunction "GND_118") (pintype "power_in"))
      (node (ref "U104") (pin "120") (pinfunction "GND_120") (pintype "power_in"))
      (node (ref "U104") (pin "121") (pinfunction "GND_121") (pintype "power_in"))
      (node (ref "U104") (pin "122") (pinfunction "GND_122") (pintype "power_in"))
      (node (ref "U104") (pin "123") (pinfunction "GND_123") (pintype "power_in"))
      (node (ref "U104") (pin "124") (pinfunction "GND_124") (pintype "power_in"))
      (node (ref "U104") (pin "125") (pinfunction "GND_125") (pintype "power_in"))
      (node (ref "U104") (pin "126") (pinfunction "GND_126") (pintype "power_in"))
      (node (ref "U104") (pin "127") (pinfunction "GND_127") (pintype "power_in"))
      (node (ref "U104") (pin "128") (pinfunction "GND_128") (pintype "power_in"))
      (node (ref "U104") (pin "129") (pinfunction "GND_129") (pintype "power_in"))
      (node (ref "U104") (pin "130") (pinfunction "GND_130") (pintype "power_in"))
      (node (ref "U104") (pin "131") (pinfunction "GND_131") (pintype "power_in"))
      (node (ref "U104") (pin "132") (pinfunction "GND_132") (pintype "power_in"))
      (node (ref "U104") (pin "133") (pinfunction "GND_133") (pintype "power_in"))
      (node (ref "U104") (pin "134") (pinfunction "GND_134") (pintype "power_in"))
      (node (ref "U104") (pin "135") (pinfunction "GND_135") (pintype "power_in"))
      (node (ref "U104") (pin "14") (pinfunction "GND_14") (pintype "power_in"))
      (node (ref "U104") (pin "2") (pinfunction "GND_2") (pintype "power_in"))
      (node (ref "U104") (pin "37") (pinfunction "GND_37") (pintype "power_in"))
      (node (ref "U104") (pin "40") (pinfunction "GND_40") (pintype "power_in"))
      (node (ref "U104") (pin "41") (pinfunction "GND_41") (pintype "power_in"))
      (node (ref "U104") (pin "43") (pinfunction "GND_43") (pintype "power_in"))
      (node (ref "U104") (pin "5") (pinfunction "GND_5") (pintype "power_in"))
      (node (ref "U104") (pin "57") (pinfunction "GND_57") (pintype "power_in"))
      (node (ref "U104") (pin "58") (pinfunction "GND_58") (pintype "power_in"))
      (node (ref "U104") (pin "60") (pinfunction "GND_60") (pintype "power_in"))
      (node (ref "U104") (pin "61") (pinfunction "GND_61") (pintype "power_in"))
      (node (ref "U104") (pin "64") (pinfunction "GND_64") (pintype "power_in"))
      (node (ref "U104") (pin "65") (pinfunction "GND_65") (pintype "power_in"))
      (node (ref "U104") (pin "77") (pinfunction "GND_77") (pintype "power_in"))
      (node (ref "U104") (pin "78") (pinfunction "GND_78") (pintype "power_in"))
      (node (ref "U104") (pin "80") (pinfunction "GND_80") (pintype "power_in"))
      (node (ref "U104") (pin "81") (pinfunction "GND_81") (pintype "power_in"))
      (node (ref "U104") (pin "93") (pinfunction "GND_93") (pintype "power_in"))
      (node (ref "U104") (pin "98") (pinfunction "GND_98") (pintype "power_in"))
      (node (ref "U105") (pin "2") (pinfunction "A_2") (pintype "passive"))
      (node (ref "U106") (pin "2") (pinfunction "A_2") (pintype "passive"))
      (node (ref "U107") (pin "11") (pinfunction "GND_11") (pintype "power_in"))
      (node (ref "U108") (pin "3") (pinfunction "GND_3_3") (pintype "power_in"))
      (node (ref "U108") (pin "8") (pinfunction "GND_8_8") (pintype "power_in"))
    )
    (net (code "34") (name "Net-(C101-Pad1)") (class "Default")
      (node (ref "C101") (pin "1") (pinfunction "1_1") (pintype "passive"))
      (node (ref "R101") (pin "2") (pinfunction "2_2") (pintype "passive"))
    )
    (net (code "35") (name "Net-(C102-Pad1)") (class "Default")
      (node (ref "C102") (pin "1") (pinfunction "1_1") (pintype "passive"))
      (node (ref "R102") (pin "2") (pinfunction "2_2") (pintype "passive"))
    )
    (net (code "36") (name "Net-(C125-Pad1)") (class "Default")
      (node (ref "C125") (pin "1") (pinfunction "1_1") (pintype "passive"))
      (node (ref "R105") (pin "2") (pinfunction "2_2") (pintype "passive"))
    )
    (net (code "37") (name "Net-(C126-Pad1)") (class "Default")
      (node (ref "C126") (pin "1") (pinfunction "1_1") (pintype "passive"))
      (node (ref "R106") (pin "2") (pinfunction "2_2") (pintype "passive"))
    )
    (net (code "38") (name "Net-(C141-Pad2)") (class "Default")
      (node (ref "C141") (pin "2") (pinfunction "2_2") (pintype "passive"))
      (node (ref "J103") (pin "1") (pinfunction "1_1") (pintype "passive"))
      (node (ref "R123") (pin "1") (pinfunction "1_1") (pintype "passive"))
    )
    (net (code "39") (name "Net-(C143-Pad2)") (class "Default")
      (node (ref "C143") (pin "2") (pinfunction "2_2") (pintype "passive"))
      (node (ref "J104") (pin "1") (pinfunction "1_1") (pintype "passive"))
      (node (ref "R124") (pin "1") (pinfunction "1_1") (pintype "passive"))
    )
    (net (code "40") (name "Net-(C145-Pad2)") (class "Default")
      (node (ref "C145") (pin "2") (pinfunction "2_2") (pintype "passive"))
      (node (ref "J105") (pin "1") (pinfunction "1_1") (pintype "passive"))
      (node (ref "L103") (pin "2") (pinfunction "2_2") (pintype "passive"))
    )
    (net (code "41") (name "Net-(C146-Pad2)") (class "Default")
      (node (ref "C146") (pin "2") (pinfunction "2_2") (pintype "passive"))
      (node (ref "J106") (pin "1") (pinfunction "1_1") (pintype "passive"))
      (node (ref "L104") (pin "2") (pinfunction "2_2") (pintype "passive"))
    )
    (net (code "42") (name "Net-(C149-Pad2)") (class "Default")
      (node (ref "C149") (pin "2") (pinfunction "2_2") (pintype "passive"))
      (node (ref "L103") (pin "1") (pinfunction "1_1") (pintype "passive"))
      (node (ref "R131") (pin "2") (pinfunction "2_2") (pintype "passive"))
    )
    (net (code "43") (name "Net-(C150-Pad2)") (class "Default")
      (node (ref "C150") (pin "2") (pinfunction "2_2") (pintype "passive"))
      (node (ref "L104") (pin "1") (pinfunction "1_1") (pintype "passive"))
      (node (ref "R132") (pin "2") (pinfunction "2_2") (pintype "passive"))
    )
    (net (code "44") (name "Net-(D103-A)") (class "Default")
      (node (ref "D103") (pin "2") (pinfunction "A_2") (pintype "passive"))
      (node (ref "R133") (pin "2") (pinfunction "2_2") (pintype "passive"))
    )
    (net (code "45") (name "Net-(D104-A)") (class "Default")
      (node (ref "D104") (pin "2") (pinfunction "A_2") (pintype "passive"))
      (node (ref "R134") (pin "2") (pinfunction "2_2") (pintype "passive"))
    )
    (net (code "46") (name "Net-(D105-A)") (class "Default")
      (node (ref "D105") (pin "2") (pinfunction "A_2") (pintype "passive"))
      (node (ref "R135") (pin "2") (pinfunction "2_2") (pintype "passive"))
    )
    (net (code "47") (name "Net-(D106-A)") (class "Default")
      (node (ref "D106") (pin "2") (pinfunction "A_2") (pintype "passive"))
      (node (ref "R136") (pin "2") (pinfunction "2_2") (pintype "passive"))
    )
    (net (code "48") (name "Net-(J101-CLK)") (class "Default")
      (node (ref "J101") (pin "C3") (pinfunction "CLK_C3") (pintype "passive"))
      (node (ref "R121") (pin "2") (pinfunction "2_2") (pintype "passive"))
      (node (ref "U105") (pin "1") (pinfunction "C1_1") (pintype "passive"))
    )
    (net (code "49") (name "Net-(J101-I{slash}O)") (class "Default")
      (node (ref "J101") (pin "C7") (pinfunction "I/O_C7") (pintype "passive"))
      (node (ref "R117") (pin "2") (pinfunction "2_2") (pintype "passive"))
      (node (ref "U105") (pin "3") (pinfunction "C2_3") (pintype "passive"))
    )
    (net (code "50") (name "Net-(J101-RST)") (class "Default")
      (node (ref "J101") (pin "C2") (pinfunction "RST_C2") (pintype "passive"))
      (node (ref "R119") (pin "2") (pinfunction "2_2") (pintype "passive"))
      (node (ref "U105") (pin "4") (pinfunction "C3_4") (pintype "passive"))
    )
    (net (code "51") (name "Net-(J101-VCC)") (class "Default")
      (node (ref "C133") (pin "1") (pinfunction "1_1") (pintype "passive"))
      (node (ref "J101") (pin "C1") (pinfunction "VCC_C1") (pintype "passive"))
      (node (ref "U103") (pin "20") (pinfunction "USIM_VDD_20") (pintype "output"))
      (node (ref "U105") (pin "6") (pinfunction "C5_6") (pintype "passive"))
    )
    (net (code "52") (name "Net-(J102-CLK)") (class "Default")
      (node (ref "J102") (pin "C3") (pinfunction "CLK_C3") (pintype "passive"))
      (node (ref "R122") (pin "2") (pinfunction "2_2") (pintype "passive"))
      (node (ref "U106") (pin "1") (pinfunction "C1_1") (pintype "passive"))
    )
    (net (code "53") (name "Net-(J102-I{slash}O)") (class "Default")
      (node (ref "J102") (pin "C7") (pinfunction "I/O_C7") (pintype "passive"))
      (node (ref "R118") (pin "2") (pinfunction "2_2") (pintype "passive"))
      (node (ref "U106") (pin "3") (pinfunction "C2_3") (pintype "passive"))
    )
    (net (code "54") (name "Net-(J102-RST)") (class "Default")
      (node (ref "J102") (pin "C2") (pinfunction "RST_C2") (pintype "passive"))
      (node (ref "R120") (pin "2") (pinfunction "2_2") (pintype "passive"))
      (node (ref "U106") (pin "4") (pinfunction "C3_4") (pintype "passive"))
    )
    (net (code "55") (name "Net-(J102-VCC)") (class "Default")
      (node (ref "C134") (pin "1") (pinfunction "1_1") (pintype "passive"))
      (node (ref "J102") (pin "C1") (pinfunction "VCC_C1") (pintype "passive"))
      (node (ref "U104") (pin "20") (pinfunction "USIM_VDD_20") (pintype "output"))
      (node (ref "U106") (pin "6") (pinfunction "C5_6") (pintype "passive"))
    )
    (net (code "56") (name "Net-(Q101-B)") (class "Default")
      (node (ref "Q101") (pin "1") (pinfunction "B_1") (pintype "passive"))
      (node (ref "R109") (pin "1") (pinfunction "1_1") (pintype "passive"))
      (node (ref "R111") (pin "2") (pinfunction "2_2") (pintype "passive"))
    )
    (net (code "57") (name "Net-(Q101-C)") (class "Default")
      (node (ref "Q101") (pin "3") (pinfunction "C_3") (pintype "passive"))
      (node (ref "U103") (pin "3") (pinfunction "~{PWRKEY}_3") (pintype "input"))
    )
    (net (code "58") (name "Net-(Q102-B)") (class "Default")
      (node (ref "Q102") (pin "1") (pinfunction "B_1") (pintype "passive"))
      (node (ref "R110") (pin "1") (pinfunction "1_1") (pintype "passive"))
      (node (ref "R112") (pin "2") (pinfunction "2_2") (pintype "passive"))
    )
    (net (code "59") (name "Net-(Q102-C)") (class "Default")
      (node (ref "Q102") (pin "3") (pinfunction "C_3") (pintype "passive"))
      (node (ref "U104") (pin "3") (pinfunction "~{PWRKEY}_3") (pintype "input"))
    )
    (net (code "60") (name "Net-(Q103-B)") (class "Default")
      (node (ref "Q103") (pin "1") (pinfunction "B_1") (pintype "passive"))
      (node (ref "R113") (pin "1") (pinfunction "1_1") (pintype "passive"))
      (node (ref "R115") (pin "2") (pinfunction "2_2") (pintype "passive"))
    )
    (net (code "61") (name "Net-(Q103-C)") (class "Default")
      (node (ref "Q103") (pin "3") (pinfunction "C_3") (pintype "passive"))
      (node (ref "U103") (pin "4") (pinfunction "~{RESET}_4") (pintype "input"))
    )
    (net (code "62") (name "Net-(Q104-B)") (class "Default")
      (node (ref "Q104") (pin "1") (pinfunction "B_1") (pintype "passive"))
      (node (ref "R114") (pin "1") (pinfunction "1_1") (pintype "passive"))
      (node (ref "R116") (pin "2") (pinfunction "2_2") (pintype "passive"))
    )
    (net (code "63") (name "Net-(Q104-C)") (class "Default")
      (node (ref "Q104") (pin "3") (pinfunction "C_3") (pintype "passive"))
      (node (ref "U104") (pin "4") (pinfunction "~{RESET}_4") (pintype "input"))
    )
    (net (code "64") (name "Net-(Q105-B)") (class "Default")
      (node (ref "Q105") (pin "1") (pinfunction "B_1") (pintype "passive"))
      (node (ref "R127") (pin "2") (pinfunction "2_2") (pintype "passive"))
      (node (ref "R129") (pin "2") (pinfunction "2_2") (pintype "passive"))
    )
    (net (code "65") (name "Net-(Q105-C)") (class "Default")
      (node (ref "C147") (pin "2") (pinfunction "2_2") (pintype "passive"))
      (node (ref "Q105") (pin "3") (pinfunction "C_3") (pintype "passive"))
      (node (ref "R125") (pin "2") (pinfunction "2_2") (pintype "passive"))
      (node (ref "U103") (pin "54") (pinfunction "FLIGHTMODE_54") (pintype "input"))
    )
    (net (code "66") (name "Net-(Q106-B)") (class "Default")
      (node (ref "Q106") (pin "1") (pinfunction "B_1") (pintype "passive"))
      (node (ref "R128") (pin "2") (pinfunction "2_2") (pintype "passive"))
      (node (ref "R130") (pin "2") (pinfunction "2_2") (pintype "passive"))
    )
    (net (code "67") (name "Net-(Q106-C)") (class "Default")
      (node (ref "C148") (pin "2") (pinfunction "2_2") (pintype "passive"))
      (node (ref "Q106") (pin "3") (pinfunction "C_3") (pintype "passive"))
      (node (ref "R126") (pin "2") (pinfunction "2_2") (pintype "passive"))
      (node (ref "U104") (pin "54") (pinfunction "FLIGHTMODE_54") (pintype "input"))
    )
    (net (code "68") (name "Net-(U101-BST)") (class "Default")
      (node (ref "C101") (pin "2") (pinfunction "2_2") (pintype "passive"))
      (node (ref "U101") (pin "1") (pinfunction "BST_1") (pintype "passive"))
    )
    (net (code "69") (name "Net-(U101-COMP)") (class "Default")
      (node (ref "C123") (pin "1") (pinfunction "1_1") (pintype "passive"))
      (node (ref "R105") (pin "1") (pinfunction "1_1") (pintype "passive"))
      (node (ref "U101") (pin "6") (pinfunction "COMP_6") (pintype "passive"))
    )
    (net (code "70") (name "Net-(U101-FB)") (class "Default")
      (node (ref "C107") (pin "2") (pinfunction "2_2") (pintype "passive"))
      (node (ref "R103") (pin "2") (pinfunction "2_2") (pintype "passive"))
      (node (ref "R107") (pin "1") (pinfunction "1_1") (pintype "passive"))
      (node (ref "U101") (pin "5") (pinfunction "FB_5") (pintype "passive"))
    )
    (net (code "71") (name "Net-(U101-SS)") (class "Default")
      (node (ref "C121") (pin "1") (pinfunction "1_1") (pintype "passive"))
      (node (ref "U101") (pin "4") (pinfunction "SS_4") (pintype "passive"))
    )
    (net (code "72") (name "Net-(U101-SW)") (class "Default")
      (node (ref "L101") (pin "1") (pinfunction "1_1") (pintype "passive"))
      (node (ref "R101") (pin "1") (pinfunction "1_1") (pintype "passive"))
      (node (ref "U101") (pin "8") (pinfunction "SW_8") (pintype "passive"))
    )
    (net (code "73") (name "Net-(U102-BST)") (class "Default")
      (node (ref "C102") (pin "2") (pinfunction "2_2") (pintype "passive"))
      (node (ref "U102") (pin "1") (pinfunction "BST_1") (pintype "passive"))
    )
    (net (code "74") (name "Net-(U102-COMP)") (class "Default")
      (node (ref "C124") (pin "1") (pinfunction "1_1") (pintype "passive"))
      (node (ref "R106") (pin "1") (pinfunction "1_1") (pintype "passive"))
      (node (ref "U102") (pin "6") (pinfunction "COMP_6") (pintype "passive"))
    )
    (net (code "75") (name "Net-(U102-FB)") (class "Default")
      (node (ref "C108") (pin "2") (pinfunction "2_2") (pintype "passive"))
      (node (ref "R104") (pin "2") (pinfunction "2_2") (pintype "passive"))
      (node (ref "R108") (pin "1") (pinfunction "1_1") (pintype "passive"))
      (node (ref "U102") (pin "5") (pinfunction "FB_5") (pintype "passive"))
    )
    (net (code "76") (name "Net-(U102-SS)") (class "Default")
      (node (ref "C122") (pin "1") (pinfunction "1_1") (pintype "passive"))
      (node (ref "U102") (pin "4") (pinfunction "SS_4") (pintype "passive"))
    )
    (net (code "77") (name "Net-(U102-SW)") (class "Default")
      (node (ref "L102") (pin "1") (pinfunction "1_1") (pintype "passive"))
      (node (ref "R102") (pin "1") (pinfunction "1_1") (pintype "passive"))
      (node (ref "U102") (pin "8") (pinfunction "SW_8") (pintype "passive"))
    )
    (net (code "78") (name "Net-(U103-GNSS_ANT)") (class "Default")
      (node (ref "C145") (pin "1") (pinfunction "1_1") (pintype "passive"))
      (node (ref "U103") (pin "79") (pinfunction "GNSS_ANT_79") (pintype "input"))
    )
    (net (code "79") (name "Net-(U103-MAIN_ANT)") (class "Default")
      (node (ref "C142") (pin "2") (pinfunction "2_2") (pintype "passive"))
      (node (ref "R123") (pin "2") (pinfunction "2_2") (pintype "passive"))
      (node (ref "U103") (pin "82") (pinfunction "MAIN_ANT_82") (pintype "bidirectional"))
    )
    (net (code "80") (name "Net-(U103-USIM_CLK)") (class "Default")
      (node (ref "C135") (pin "2") (pinfunction "2_2") (pintype "passive"))
      (node (ref "R121") (pin "1") (pinfunction "1_1") (pintype "passive"))
      (node (ref "U103") (pin "19") (pinfunction "USIM_CLK_19") (pintype "output"))
    )
    (net (code "81") (name "Net-(U103-USIM_DATA)") (class "Default")
      (node (ref "C137") (pin "2") (pinfunction "2_2") (pintype "passive"))
      (node (ref "R117") (pin "1") (pinfunction "1_1") (pintype "passive"))
      (node (ref "U103") (pin "17") (pinfunction "USIM_DATA_17") (pintype "bidirectional"))
    )
    (net (code "82") (name "Net-(U103-USIM_RST)") (class "Default")
      (node (ref "C136") (pin "2") (pinfunction "2_2") (pintype "passive"))
      (node (ref "R119") (pin "1") (pinfunction "1_1") (pintype "passive"))
      (node (ref "U103") (pin "18") (pinfunction "USIM_RST_18") (pintype "output"))
    )
    (net (code "83") (name "Net-(U104-GNSS_ANT)") (class "Default")
      (node (ref "C146") (pin "1") (pinfunction "1_1") (pintype "passive"))
      (node (ref "U104") (pin "79") (pinfunction "GNSS_ANT_79") (pintype "input"))
    )
    (net (code "84") (name "Net-(U104-MAIN_ANT)") (class "Default")
      (node (ref "C144") (pin "2") (pinfunction "2_2") (pintype "passive"))
      (node (ref "R124") (pin "2") (pinfunction "2_2") (pintype "passive"))
      (node (ref "U104") (pin "82") (pinfunction "MAIN_ANT_82") (pintype "bidirectional"))
    )
    (net (code "85") (name "Net-(U104-USIM_CLK)") (class "Default")
      (node (ref "C138") (pin "2") (pinfunction "2_2") (pintype "passive"))
      (node (ref "R122") (pin "1") (pinfunction "1_1") (pintype "passive"))
      (node (ref "U104") (pin "19") (pinfunction "USIM_CLK_19") (pintype "output"))
    )
    (net (code "86") (name "Net-(U104-USIM_DATA)") (class "Default")
      (node (ref "C140") (pin "2") (pinfunction "2_2") (pintype "passive"))
      (node (ref "R118") (pin "1") (pinfunction "1_1") (pintype "passive"))
      (node (ref "U104") (pin "17") (pinfunction "USIM_DATA_17") (pintype "bidirectional"))
    )
    (net (code "87") (name "Net-(U104-USIM_RST)") (class "Default")
      (node (ref "C139") (pin "2") (pinfunction "2_2") (pintype "passive"))
      (node (ref "R120") (pin "1") (pinfunction "1_1") (pintype "passive"))
      (node (ref "U104") (pin "18") (pinfunction "USIM_RST_18") (pintype "output"))
    )
    (net (code "88") (name "VBUS") (class "Default")
      (node (ref "U103") (pin "11") (pinfunction "USB_VBUS_11") (pintype "input"))
      (node (ref "U104") (pin "11") (pinfunction "USB_VBUS_11") (pintype "input"))
    )
    (net (code "89") (name "VDD_1V8_1") (class "Default")
      (node (ref "C152") (pin "1") (pinfunction "1_1") (pintype "passive"))
      (node (ref "R125") (pin "1") (pinfunction "1_1") (pintype "passive"))
      (node (ref "U103") (pin "15") (pinfunction "VDD_1V8_15") (pintype "output"))
      (node (ref "U107") (pin "10") (pinfunction "OE_10") (pintype "input"))
      (node (ref "U107") (pin "2") (pinfunction "VCCA_2") (pintype "power_in"))
    )
    (net (code "90") (name "VDD_1V8_2") (class "Default")
      (node (ref "R126") (pin "1") (pinfunction "1_1") (pintype "passive"))
      (node (ref "U104") (pin "15") (pinfunction "VDD_1V8_15") (pintype "output"))
    )
    (net (code "91") (name "VLTE_1") (class "Default")
      (node (ref "C103") (pin "1") (pinfunction "1_1") (pintype "passive"))
      (node (ref "C104") (pin "1") (pinfunction "1_1") (pintype "passive"))
      (node (ref "C107") (pin "1") (pinfunction "1_1") (pintype "passive"))
      (node (ref "C127") (pin "1") (pinfunction "1_1") (pintype "passive"))
      (node (ref "C128") (pin "1") (pinfunction "1_1") (pintype "passive"))
      (node (ref "C131") (pin "1") (pinfunction "1_1") (pintype "passive"))
      (node (ref "D101") (pin "K") (pinfunction "K_K") (pintype "passive"))
      (node (ref "L101") (pin "2") (pinfunction "2_2") (pintype "passive"))
      (node (ref "R103") (pin "1") (pinfunction "1_1") (pintype "passive"))
      (node (ref "U103") (pin "38") (pinfunction "VBAT_38") (pintype "power_in"))
      (node (ref "U103") (pin "39") (pinfunction "VBAT_39") (pintype "power_in"))
      (node (ref "U103") (pin "62") (pinfunction "VBAT_62") (pintype "power_in"))
      (node (ref "U103") (pin "63") (pinfunction "VBAT_63") (pintype "power_in"))
    )
    (net (code "92") (name "VLTE_2") (class "Default")
      (node (ref "C105") (pin "1") (pinfunction "1_1") (pintype "passive"))
      (node (ref "C106") (pin "1") (pinfunction "1_1") (pintype "passive"))
      (node (ref "C108") (pin "1") (pinfunction "1_1") (pintype "passive"))
      (node (ref "C129") (pin "1") (pinfunction "1_1") (pintype "passive"))
      (node (ref "C130") (pin "1") (pinfunction "1_1") (pintype "passive"))
      (node (ref "C132") (pin "1") (pinfunction "1_1") (pintype "passive"))
      (node (ref "D102") (pin "K") (pinfunction "K_K") (pintype "passive"))
      (node (ref "L102") (pin "2") (pinfunction "2_2") (pintype "passive"))
      (node (ref "R104") (pin "1") (pinfunction "1_1") (pintype "passive"))
      (node (ref "U104") (pin "38") (pinfunction "VBAT_38") (pintype "power_in"))
      (node (ref "U104") (pin "39") (pinfunction "VBAT_39") (pintype "power_in"))
      (node (ref "U104") (pin "62") (pinfunction "VBAT_62") (pintype "power_in"))
      (node (ref "U104") (pin "63") (pinfunction "VBAT_63") (pintype "power_in"))
    )
    (net (code "93") (name "unconnected-(J101-VPP-PadC6)") (class "Default")
      (node (ref "J101") (pin "C6") (pinfunction "VPP_C6") (pintype "passive"))
    )
    (net (code "94") (name "unconnected-(J102-VPP-PadC6)") (class "Default")
      (node (ref "J102") (pin "C6") (pinfunction "VPP_C6") (pintype "passive"))
    )
    (net (code "95") (name "unconnected-(U103-ADC1-Pad47)") (class "Default")
      (node (ref "U103") (pin "47") (pinfunction "ADC1_47") (pintype "input"))
    )
    (net (code "96") (name "unconnected-(U103-ADC2-Pad46)") (class "Default")
      (node (ref "U103") (pin "46") (pinfunction "ADC2_46") (pintype "input"))
    )
    (net (code "97") (name "unconnected-(U103-AUX_ANT-Pad59)") (class "Default")
      (node (ref "U103") (pin "59") (pinfunction "AUX_ANT_59") (pintype "input"))
    )
    (net (code "98") (name "unconnected-(U103-BOOT_CFG0{slash}USB_BOOT-Pad85)") (class "Default")
      (node (ref "U103") (pin "85") (pinfunction "BOOT_CFG0/USB_BOOT_85") (pintype "input"))
    )
    (net (code "99") (name "unconnected-(U103-COEX1-Pad83)") (class "Default")
      (node (ref "U103") (pin "83") (pinfunction "COEX1_83") (pintype "bidirectional"))
    )
    (net (code "100") (name "unconnected-(U103-COEX2-Pad84)") (class "Default")
      (node (ref "U103") (pin "84") (pinfunction "COEX2_84") (pintype "bidirectional"))
    )
    (net (code "101") (name "unconnected-(U103-COEX3-Pad86)") (class "Default")
      (node (ref "U103") (pin "86") (pinfunction "COEX3_86") (pintype "bidirectional"))
    )
    (net (code "102") (name "unconnected-(U103-DBG_RXD-Pad106)") (class "Default")
      (node (ref "U103") (pin "106") (pinfunction "DBG_RXD_106") (pintype "input"))
    )
    (net (code "103") (name "unconnected-(U103-DBG_TXD-Pad42)") (class "Default")
      (node (ref "U103") (pin "42") (pinfunction "DBG_TXD_42") (pintype "output"))
    )
    (net (code "104") (name "unconnected-(U103-DCD-Pad70)") (class "Default")
      (node (ref "U103") (pin "70") (pinfunction "DCD_70") (pintype "output"))
    )
    (net (code "105") (name "unconnected-(U103-DTR-Pad72)") (class "Default")
      (node (ref "U103") (pin "72") (pinfunction "DTR_72") (pintype "input"))
    )
    (net (code "106") (name "unconnected-(U103-GPIO1-Pad96)") (class "Default")
      (node (ref "U103") (pin "96") (pinfunction "GPIO1_96") (pintype "bidirectional"))
    )
    (net (code "107") (name "unconnected-(U103-GPIO2-Pad95)") (class "Default")
      (node (ref "U103") (pin "95") (pinfunction "GPIO2_95") (pintype "bidirectional"))
    )
    (net (code "108") (name "unconnected-(U103-GPIO3-Pad33)") (class "Default")
      (node (ref "U103") (pin "33") (pinfunction "GPIO3_33") (pintype "bidirectional"))
    )
    (net (code "109") (name "unconnected-(U103-GPIO4-Pad94)") (class "Default")
      (node (ref "U103") (pin "94") (pinfunction "GPIO4_94") (pintype "bidirectional"))
    )
    (net (code "110") (name "unconnected-(U103-GPIO6-Pad34)") (class "Default")
      (node (ref "U103") (pin "34") (pinfunction "GPIO6_34") (pintype "bidirectional"))
    )
    (net (code "111") (name "unconnected-(U103-GPIO41-Pad52)") (class "Default")
      (node (ref "U103") (pin "52") (pinfunction "GPIO41_52") (pintype "bidirectional"))
    )
    (net (code "112") (name "unconnected-(U103-GPIO43-Pad50)") (class "Default")
      (node (ref "U103") (pin "50") (pinfunction "GPIO43_50") (pintype "bidirectional"))
    )
    (net (code "113") (name "unconnected-(U103-GPIO77-Pad87)") (class "Default")
      (node (ref "U103") (pin "87") (pinfunction "GPIO77_87") (pintype "bidirectional"))
    )
    (net (code "114") (name "unconnected-(U103-GPIO_19-Pad119)") (class "Default")
      (node (ref "U103") (pin "119") (pinfunction "GPIO_19_119") (pintype "bidirectional"))
    )
    (net (code "115") (name "unconnected-(U103-GPIO_54-Pad97)") (class "Default")
      (node (ref "U103") (pin "97") (pinfunction "GPIO_54_97") (pintype "bidirectional"))
    )
    (net (code "116") (name "unconnected-(U103-HSIC_DATA-Pad36)") (class "Default")
      (node (ref "U103") (pin "36") (pinfunction "HSIC_DATA_36") (pintype "bidirectional"))
    )
    (net (code "117") (name "unconnected-(U103-HSIC_STROBE-Pad35)") (class "Default")
      (node (ref "U103") (pin "35") (pinfunction "HSIC_STROBE_35") (pintype "bidirectional"))
    )
    (net (code "118") (name "unconnected-(U103-ISINK-Pad45)") (class "Default")
      (node (ref "U103") (pin "45") (pinfunction "ISINK_45") (pintype "input"))
    )
    (net (code "119") (name "unconnected-(U103-NC-Pad107)") (class "Default")
      (node (ref "U103") (pin "107") (pinfunction "NC_107") (pintype "passive"))
    )
    (net (code "120") (name "unconnected-(U103-PCM_CLK-Pad76)") (class "Default")
      (node (ref "U103") (pin "76") (pinfunction "PCM_CLK_76") (pintype "bidirectional"))
    )
    (net (code "121") (name "unconnected-(U103-PCM_IN-Pad74)") (class "Default")
      (node (ref "U103") (pin "74") (pinfunction "PCM_IN_74") (pintype "input"))
    )
    (net (code "122") (name "unconnected-(U103-PCM_OUT-Pad73)") (class "Default")
      (node (ref "U103") (pin "73") (pinfunction "PCM_OUT_73") (pintype "output"))
    )
    (net (code "123") (name "unconnected-(U103-PCM_SYNC-Pad75)") (class "Default")
      (node (ref "U103") (pin "75") (pinfunction "PCM_SYNC_75") (pintype "bidirectional"))
    )
    (net (code "124") (name "unconnected-(U103-RESERVED-Pad88)") (class "Default")
      (node (ref "U103") (pin "88") (pinfunction "RESERVED_88") (pintype "passive"))
    )
    (net (code "125") (name "unconnected-(U103-RESERVED-Pad89)") (class "Default")
      (node (ref "U103") (pin "89") (pinfunction "RESERVED_89") (pintype "passive"))
    )
    (net (code "126") (name "unconnected-(U103-RESERVED-Pad90)") (class "Default")
      (node (ref "U103") (pin "90") (pinfunction "RESERVED_90") (pintype "passive"))
    )
    (net (code "127") (name "unconnected-(U103-RESERVED-Pad91)") (class "Default")
      (node (ref "U103") (pin "91") (pinfunction "RESERVED_91") (pintype "passive"))
    )
    (net (code "128") (name "unconnected-(U103-RESERVED-Pad92)") (class "Default")
      (node (ref "U103") (pin "92") (pinfunction "RESERVED_92") (pintype "passive"))
    )
    (net (code "129") (name "unconnected-(U103-RESERVED-Pad99)") (class "Default")
      (node (ref "U103") (pin "99") (pinfunction "RESERVED_99") (pintype "passive"))
    )
    (net (code "130") (name "unconnected-(U103-RESERVED-Pad100)") (class "Default")
      (node (ref "U103") (pin "100") (pinfunction "RESERVED_100") (pintype "passive"))
    )
    (net (code "131") (name "unconnected-(U103-RESERVED-Pad101)") (class "Default")
      (node (ref "U103") (pin "101") (pinfunction "RESERVED_101") (pintype "passive"))
    )
    (net (code "132") (name "unconnected-(U103-RESERVED-Pad102)") (class "Default")
      (node (ref "U103") (pin "102") (pinfunction "RESERVED_102") (pintype "passive"))
    )
    (net (code "133") (name "unconnected-(U103-RESERVED-Pad103)") (class "Default")
      (node (ref "U103") (pin "103") (pinfunction "RESERVED_103") (pintype "passive"))
    )
    (net (code "134") (name "unconnected-(U103-RESERVED-Pad104)") (class "Default")
      (node (ref "U103") (pin "104") (pinfunction "RESERVED_104") (pintype "passive"))
    )
    (net (code "135") (name "unconnected-(U103-RESERVED-Pad105)") (class "Default")
      (node (ref "U103") (pin "105") (pinfunction "RESERVED_105") (pintype "passive"))
    )
    (net (code "136") (name "unconnected-(U103-RESERVED-Pad111)") (class "Default")
      (node (ref "U103") (pin "111") (pinfunction "RESERVED_111") (pintype "passive"))
    )
    (net (code "137") (name "unconnected-(U103-RI-Pad69)") (class "Default")
      (node (ref "U103") (pin "69") (pinfunction "RI_69") (pintype "output"))
    )
    (net (code "138") (name "unconnected-(U103-SCL-Pad55)") (class "Default")
      (node (ref "U103") (pin "55") (pinfunction "SCL_55") (pintype "output"))
    )
    (net (code "139") (name "unconnected-(U103-SDA-Pad56)") (class "Default")
      (node (ref "U103") (pin "56") (pinfunction "SDA_56") (pintype "bidirectional"))
    )
    (net (code "140") (name "unconnected-(U103-SDIO_CLK-Pad32)") (class "Default")
      (node (ref "U103") (pin "32") (pinfunction "SDIO_CLK_32") (pintype "output"))
    )
    (net (code "141") (name "unconnected-(U103-SDIO_CMD-Pad29)") (class "Default")
      (node (ref "U103") (pin "29") (pinfunction "SDIO_CMD_29") (pintype "bidirectional"))
    )
    (net (code "142") (name "unconnected-(U103-SDIO_DATA0-Pad30)") (class "Default")
      (node (ref "U103") (pin "30") (pinfunction "SDIO_DATA0_30") (pintype "bidirectional"))
    )
    (net (code "143") (name "unconnected-(U103-SDIO_DATA1-Pad27)") (class "Default")
      (node (ref "U103") (pin "27") (pinfunction "SDIO_DATA1_27") (pintype "bidirectional"))
    )
    (net (code "144") (name "unconnected-(U103-SDIO_DATA2-Pad28)") (class "Default")
      (node (ref "U103") (pin "28") (pinfunction "SDIO_DATA2_28") (pintype "bidirectional"))
    )
    (net (code "145") (name "unconnected-(U103-SDIO_DATA3-Pad31)") (class "Default")
      (node (ref "U103") (pin "31") (pinfunction "SDIO_DATA3_31") (pintype "bidirectional"))
    )
    (net (code "146") (name "unconnected-(U103-SD_CLK-Pad26)") (class "Default")
      (node (ref "U103") (pin "26") (pinfunction "SD_CLK_26") (pintype "output"))
    )
    (net (code "147") (name "unconnected-(U103-SD_CMD-Pad21)") (class "Default")
      (node (ref "U103") (pin "21") (pinfunction "SD_CMD_21") (pintype "bidirectional"))
    )
    (net (code "148") (name "unconnected-(U103-SD_DATA0-Pad22)") (class "Default")
      (node (ref "U103") (pin "22") (pinfunction "SD_DATA0_22") (pintype "bidirectional"))
    )
    (net (code "149") (name "unconnected-(U103-SD_DATA1-Pad23)") (class "Default")
      (node (ref "U103") (pin "23") (pinfunction "SD_DATA1_23") (pintype "bidirectional"))
    )
    (net (code "150") (name "unconnected-(U103-SD_DATA2-Pad24)") (class "Default")
      (node (ref "U103") (pin "24") (pinfunction "SD_DATA2_24") (pintype "bidirectional"))
    )
    (net (code "151") (name "unconnected-(U103-SD_DATA3-Pad25)") (class "Default")
      (node (ref "U103") (pin "25") (pinfunction "SD_DATA3_25") (pintype "bidirectional"))
    )
    (net (code "152") (name "unconnected-(U103-SD_DET-Pad48)") (class "Default")
      (node (ref "U103") (pin "48") (pinfunction "SD_DET_48") (pintype "input"))
    )
    (net (code "153") (name "unconnected-(U103-SGMII_INT_N-Pad109)") (class "Default")
      (node (ref "U103") (pin "109") (pinfunction "SGMII_INT_N_109") (pintype "bidirectional"))
    )
    (net (code "154") (name "unconnected-(U103-SGMII_MDC-Pad117)") (class "Default")
      (node (ref "U103") (pin "117") (pinfunction "SGMII_MDC_117") (pintype "bidirectional"))
    )
    (net (code "155") (name "unconnected-(U103-SGMII_MDIO-Pad116)") (class "Default")
      (node (ref "U103") (pin "116") (pinfunction "SGMII_MDIO_116") (pintype "bidirectional"))
    )
    (net (code "156") (name "unconnected-(U103-SGMII_RST_N-Pad108)") (class "Default")
      (node (ref "U103") (pin "108") (pinfunction "SGMII_RST_N_108") (pintype "bidirectional"))
    )
    (net (code "157") (name "unconnected-(U103-SGMII_RX_M-Pad113)") (class "Default")
      (node (ref "U103") (pin "113") (pinfunction "SGMII_RX_M_113") (pintype "bidirectional"))
    )
    (net (code "158") (name "unconnected-(U103-SGMII_RX_P-Pad112)") (class "Default")
      (node (ref "U103") (pin "112") (pinfunction "SGMII_RX_P_112") (pintype "bidirectional"))
    )
    (net (code "159") (name "unconnected-(U103-SGMII_TX_M-Pad114)") (class "Default")
      (node (ref "U103") (pin "114") (pinfunction "SGMII_TX_M_114") (pintype "bidirectional"))
    )
    (net (code "160") (name "unconnected-(U103-SGMII_TX_P-Pad115)") (class "Default")
      (node (ref "U103") (pin "115") (pinfunction "SGMII_TX_P_115") (pintype "bidirectional"))
    )
    (net (code "161") (name "unconnected-(U103-SPI_CLK-Pad6)") (class "Default")
      (node (ref "U103") (pin "6") (pinfunction "SPI_CLK_6") (pintype "output"))
    )
    (net (code "162") (name "unconnected-(U103-SPI_CS-Pad9)") (class "Default")
      (node (ref "U103") (pin "9") (pinfunction "SPI_CS_9") (pintype "output"))
    )
    (net (code "163") (name "unconnected-(U103-SPI_MISO-Pad7)") (class "Default")
      (node (ref "U103") (pin "7") (pinfunction "SPI_MISO_7") (pintype "input"))
    )
    (net (code "164") (name "unconnected-(U103-SPI_MOSI-Pad8)") (class "Default")
      (node (ref "U103") (pin "8") (pinfunction "SPI_MOSI_8") (pintype "output"))
    )
    (net (code "165") (name "unconnected-(U103-USB_ID-Pad16)") (class "Default")
      (node (ref "U103") (pin "16") (pinfunction "USB_ID_16") (pintype "input"))
    )
    (net (code "166") (name "unconnected-(U103-USIM_DET-Pad53)") (class "Default")
      (node (ref "U103") (pin "53") (pinfunction "USIM_DET_53") (pintype "bidirectional"))
    )
    (net (code "167") (name "unconnected-(U103-VDD_AUX-Pad44)") (class "Default")
      (node (ref "U103") (pin "44") (pinfunction "VDD_AUX_44") (pintype "output"))
    )
    (net (code "168") (name "unconnected-(U104-ADC1-Pad47)") (class "Default")
      (node (ref "U104") (pin "47") (pinfunction "ADC1_47") (pintype "input"))
    )
    (net (code "169") (name "unconnected-(U104-ADC2-Pad46)") (class "Default")
      (node (ref "U104") (pin "46") (pinfunction "ADC2_46") (pintype "input"))
    )
    (net (code "170") (name "unconnected-(U104-AUX_ANT-Pad59)") (class "Default")
      (node (ref "U104") (pin "59") (pinfunction "AUX_ANT_59") (pintype "input"))
    )
    (net (code "171") (name "unconnected-(U104-BOOT_CFG0{slash}USB_BOOT-Pad85)") (class "Default")
      (node (ref "U104") (pin "85") (pinfunction "BOOT_CFG0/USB_BOOT_85") (pintype "input"))
    )
    (net (code "172") (name "unconnected-(U104-COEX1-Pad83)") (class "Default")
      (node (ref "U104") (pin "83") (pinfunction "COEX1_83") (pintype "bidirectional"))
    )
    (net (code "173") (name "unconnected-(U104-COEX2-Pad84)") (class "Default")
      (node (ref "U104") (pin "84") (pinfunction "COEX2_84") (pintype "bidirectional"))
    )
    (net (code "174") (name "unconnected-(U104-COEX3-Pad86)") (class "Default")
      (node (ref "U104") (pin "86") (pinfunction "COEX3_86") (pintype "bidirectional"))
    )
    (net (code "175") (name "unconnected-(U104-DBG_RXD-Pad106)") (class "Default")
      (node (ref "U104") (pin "106") (pinfunction "DBG_RXD_106") (pintype "input"))
    )
    (net (code "176") (name "unconnected-(U104-DBG_TXD-Pad42)") (class "Default")
      (node (ref "U104") (pin "42") (pinfunction "DBG_TXD_42") (pintype "output"))
    )
    (net (code "177") (name "unconnected-(U104-DCD-Pad70)") (class "Default")
      (node (ref "U104") (pin "70") (pinfunction "DCD_70") (pintype "output"))
    )
    (net (code "178") (name "unconnected-(U104-DTR-Pad72)") (class "Default")
      (node (ref "U104") (pin "72") (pinfunction "DTR_72") (pintype "input"))
    )
    (net (code "179") (name "unconnected-(U104-GPIO1-Pad96)") (class "Default")
      (node (ref "U104") (pin "96") (pinfunction "GPIO1_96") (pintype "bidirectional"))
    )
    (net (code "180") (name "unconnected-(U104-GPIO2-Pad95)") (class "Default")
      (node (ref "U104") (pin "95") (pinfunction "GPIO2_95") (pintype "bidirectional"))
    )
    (net (code "181") (name "unconnected-(U104-GPIO3-Pad33)") (class "Default")
      (node (ref "U104") (pin "33") (pinfunction "GPIO3_33") (pintype "bidirectional"))
    )
    (net (code "182") (name "unconnected-(U104-GPIO4-Pad94)") (class "Default")
      (node (ref "U104") (pin "94") (pinfunction "GPIO4_94") (pintype "bidirectional"))
    )
    (net (code "183") (name "unconnected-(U104-GPIO6-Pad34)") (class "Default")
      (node (ref "U104") (pin "34") (pinfunction "GPIO6_34") (pintype "bidirectional"))
    )
    (net (code "184") (name "unconnected-(U104-GPIO41-Pad52)") (class "Default")
      (node (ref "U104") (pin "52") (pinfunction "GPIO41_52") (pintype "bidirectional"))
    )
    (net (code "185") (name "unconnected-(U104-GPIO43-Pad50)") (class "Default")
      (node (ref "U104") (pin "50") (pinfunction "GPIO43_50") (pintype "bidirectional"))
    )
    (net (code "186") (name "unconnected-(U104-GPIO77-Pad87)") (class "Default")
      (node (ref "U104") (pin "87") (pinfunction "GPIO77_87") (pintype "bidirectional"))
    )
    (net (code "187") (name "unconnected-(U104-GPIO_19-Pad119)") (class "Default")
      (node (ref "U104") (pin "119") (pinfunction "GPIO_19_119") (pintype "bidirectional"))
    )
    (net (code "188") (name "unconnected-(U104-GPIO_54-Pad97)") (class "Default")
      (node (ref "U104") (pin "97") (pinfunction "GPIO_54_97") (pintype "bidirectional"))
    )
    (net (code "189") (name "unconnected-(U104-HSIC_DATA-Pad36)") (class "Default")
      (node (ref "U104") (pin "36") (pinfunction "HSIC_DATA_36") (pintype "bidirectional"))
    )
    (net (code "190") (name "unconnected-(U104-HSIC_STROBE-Pad35)") (class "Default")
      (node (ref "U104") (pin "35") (pinfunction "HSIC_STROBE_35") (pintype "bidirectional"))
    )
    (net (code "191") (name "unconnected-(U104-ISINK-Pad45)") (class "Default")
      (node (ref "U104") (pin "45") (pinfunction "ISINK_45") (pintype "input"))
    )
    (net (code "192") (name "unconnected-(U104-NC-Pad107)") (class "Default")
      (node (ref "U104") (pin "107") (pinfunction "NC_107") (pintype "passive"))
    )
    (net (code "193") (name "unconnected-(U104-PCM_CLK-Pad76)") (class "Default")
      (node (ref "U104") (pin "76") (pinfunction "PCM_CLK_76") (pintype "bidirectional"))
    )
    (net (code "194") (name "unconnected-(U104-PCM_IN-Pad74)") (class "Default")
      (node (ref "U104") (pin "74") (pinfunction "PCM_IN_74") (pintype "input"))
    )
    (net (code "195") (name "unconnected-(U104-PCM_OUT-Pad73)") (class "Default")
      (node (ref "U104") (pin "73") (pinfunction "PCM_OUT_73") (pintype "output"))
    )
    (net (code "196") (name "unconnected-(U104-PCM_SYNC-Pad75)") (class "Default")
      (node (ref "U104") (pin "75") (pinfunction "PCM_SYNC_75") (pintype "bidirectional"))
    )
    (net (code "197") (name "unconnected-(U104-RESERVED-Pad88)") (class "Default")
      (node (ref "U104") (pin "88") (pinfunction "RESERVED_88") (pintype "passive"))
    )
    (net (code "198") (name "unconnected-(U104-RESERVED-Pad89)") (class "Default")
      (node (ref "U104") (pin "89") (pinfunction "RESERVED_89") (pintype "passive"))
    )
    (net (code "199") (name "unconnected-(U104-RESERVED-Pad90)") (class "Default")
      (node (ref "U104") (pin "90") (pinfunction "RESERVED_90") (pintype "passive"))
    )
    (net (code "200") (name "unconnected-(U104-RESERVED-Pad91)") (class "Default")
      (node (ref "U104") (pin "91") (pinfunction "RESERVED_91") (pintype "passive"))
    )
    (net (code "201") (name "unconnected-(U104-RESERVED-Pad92)") (class "Default")
      (node (ref "U104") (pin "92") (pinfunction "RESERVED_92") (pintype "passive"))
    )
    (net (code "202") (name "unconnected-(U104-RESERVED-Pad99)") (class "Default")
      (node (ref "U104") (pin "99") (pinfunction "RESERVED_99") (pintype "passive"))
    )
    (net (code "203") (name "unconnected-(U104-RESERVED-Pad100)") (class "Default")
      (node (ref "U104") (pin "100") (pinfunction "RESERVED_100") (pintype "passive"))
    )
    (net (code "204") (name "unconnected-(U104-RESERVED-Pad101)") (class "Default")
      (node (ref "U104") (pin "101") (pinfunction "RESERVED_101") (pintype "passive"))
    )
    (net (code "205") (name "unconnected-(U104-RESERVED-Pad102)") (class "Default")
      (node (ref "U104") (pin "102") (pinfunction "RESERVED_102") (pintype "passive"))
    )
    (net (code "206") (name "unconnected-(U104-RESERVED-Pad103)") (class "Default")
      (node (ref "U104") (pin "103") (pinfunction "RESERVED_103") (pintype "passive"))
    )
    (net (code "207") (name "unconnected-(U104-RESERVED-Pad104)") (class "Default")
      (node (ref "U104") (pin "104") (pinfunction "RESERVED_104") (pintype "passive"))
    )
    (net (code "208") (name "unconnected-(U104-RESERVED-Pad105)") (class "Default")
      (node (ref "U104") (pin "105") (pinfunction "RESERVED_105") (pintype "passive"))
    )
    (net (code "209") (name "unconnected-(U104-RESERVED-Pad111)") (class "Default")
      (node (ref "U104") (pin "111") (pinfunction "RESERVED_111") (pintype "passive"))
    )
    (net (code "210") (name "unconnected-(U104-RI-Pad69)") (class "Default")
      (node (ref "U104") (pin "69") (pinfunction "RI_69") (pintype "output"))
    )
    (net (code "211") (name "unconnected-(U104-SCL-Pad55)") (class "Default")
      (node (ref "U104") (pin "55") (pinfunction "SCL_55") (pintype "output"))
    )
    (net (code "212") (name "unconnected-(U104-SDA-Pad56)") (class "Default")
      (node (ref "U104") (pin "56") (pinfunction "SDA_56") (pintype "bidirectional"))
    )
    (net (code "213") (name "unconnected-(U104-SDIO_CLK-Pad32)") (class "Default")
      (node (ref "U104") (pin "32") (pinfunction "SDIO_CLK_32") (pintype "output"))
    )
    (net (code "214") (name "unconnected-(U104-SDIO_CMD-Pad29)") (class "Default")
      (node (ref "U104") (pin "29") (pinfunction "SDIO_CMD_29") (pintype "bidirectional"))
    )
    (net (code "215") (name "unconnected-(U104-SDIO_DATA0-Pad30)") (class "Default")
      (node (ref "U104") (pin "30") (pinfunction "SDIO_DATA0_30") (pintype "bidirectional"))
    )
    (net (code "216") (name "unconnected-(U104-SDIO_DATA1-Pad27)") (class "Default")
      (node (ref "U104") (pin "27") (pinfunction "SDIO_DATA1_27") (pintype "bidirectional"))
    )
    (net (code "217") (name "unconnected-(U104-SDIO_DATA2-Pad28)") (class "Default")
      (node (ref "U104") (pin "28") (pinfunction "SDIO_DATA2_28") (pintype "bidirectional"))
    )
    (net (code "218") (name "unconnected-(U104-SDIO_DATA3-Pad31)") (class "Default")
      (node (ref "U104") (pin "31") (pinfunction "SDIO_DATA3_31") (pintype "bidirectional"))
    )
    (net (code "219") (name "unconnected-(U104-SD_CLK-Pad26)") (class "Default")
      (node (ref "U104") (pin "26") (pinfunction "SD_CLK_26") (pintype "output"))
    )
    (net (code "220") (name "unconnected-(U104-SD_CMD-Pad21)") (class "Default")
      (node (ref "U104") (pin "21") (pinfunction "SD_CMD_21") (pintype "bidirectional"))
    )
    (net (code "221") (name "unconnected-(U104-SD_DATA0-Pad22)") (class "Default")
      (node (ref "U104") (pin "22") (pinfunction "SD_DATA0_22") (pintype "bidirectional"))
    )
    (net (code "222") (name "unconnected-(U104-SD_DATA1-Pad23)") (class "Default")
      (node (ref "U104") (pin "23") (pinfunction "SD_DATA1_23") (pintype "bidirectional"))
    )
    (net (code "223") (name "unconnected-(U104-SD_DATA2-Pad24)") (class "Default")
      (node (ref "U104") (pin "24") (pinfunction "SD_DATA2_24") (pintype "bidirectional"))
    )
    (net (code "224") (name "unconnected-(U104-SD_DATA3-Pad25)") (class "Default")
      (node (ref "U104") (pin "25") (pinfunction "SD_DATA3_25") (pintype "bidirectional"))
    )
    (net (code "225") (name "unconnected-(U104-SD_DET-Pad48)") (class "Default")
      (node (ref "U104") (pin "48") (pinfunction "SD_DET_48") (pintype "input"))
    )
    (net (code "226") (name "unconnected-(U104-SGMII_INT_N-Pad109)") (class "Default")
      (node (ref "U104") (pin "109") (pinfunction "SGMII_INT_N_109") (pintype "bidirectional"))
    )
    (net (code "227") (name "unconnected-(U104-SGMII_MDC-Pad117)") (class "Default")
      (node (ref "U104") (pin "117") (pinfunction "SGMII_MDC_117") (pintype "bidirectional"))
    )
    (net (code "228") (name "unconnected-(U104-SGMII_MDIO-Pad116)") (class "Default")
      (node (ref "U104") (pin "116") (pinfunction "SGMII_MDIO_116") (pintype "bidirectional"))
    )
    (net (code "229") (name "unconnected-(U104-SGMII_RST_N-Pad108)") (class "Default")
      (node (ref "U104") (pin "108") (pinfunction "SGMII_RST_N_108") (pintype "bidirectional"))
    )
    (net (code "230") (name "unconnected-(U104-SGMII_RX_M-Pad113)") (class "Default")
      (node (ref "U104") (pin "113") (pinfunction "SGMII_RX_M_113") (pintype "bidirectional"))
    )
    (net (code "231") (name "unconnected-(U104-SGMII_RX_P-Pad112)") (class "Default")
      (node (ref "U104") (pin "112") (pinfunction "SGMII_RX_P_112") (pintype "bidirectional"))
    )
    (net (code "232") (name "unconnected-(U104-SGMII_TX_M-Pad114)") (class "Default")
      (node (ref "U104") (pin "114") (pinfunction "SGMII_TX_M_114") (pintype "bidirectional"))
    )
    (net (code "233") (name "unconnected-(U104-SGMII_TX_P-Pad115)") (class "Default")
      (node (ref "U104") (pin "115") (pinfunction "SGMII_TX_P_115") (pintype "bidirectional"))
    )
    (net (code "234") (name "unconnected-(U104-SPI_CLK-Pad6)") (class "Default")
      (node (ref "U104") (pin "6") (pinfunction "SPI_CLK_6") (pintype "output"))
    )
    (net (code "235") (name "unconnected-(U104-SPI_CS-Pad9)") (class "Default")
      (node (ref "U104") (pin "9") (pinfunction "SPI_CS_9") (pintype "output"))
    )
    (net (code "236") (name "unconnected-(U104-SPI_MISO-Pad7)") (class "Default")
      (node (ref "U104") (pin "7") (pinfunction "SPI_MISO_7") (pintype "input"))
    )
    (net (code "237") (name "unconnected-(U104-SPI_MOSI-Pad8)") (class "Default")
      (node (ref "U104") (pin "8") (pinfunction "SPI_MOSI_8") (pintype "output"))
    )
    (net (code "238") (name "unconnected-(U104-USB_ID-Pad16)") (class "Default")
      (node (ref "U104") (pin "16") (pinfunction "USB_ID_16") (pintype "input"))
    )
    (net (code "239") (name "unconnected-(U104-USIM_DET-Pad53)") (class "Default")
      (node (ref "U104") (pin "53") (pinfunction "USIM_DET_53") (pintype "bidirectional"))
    )
    (net (code "240") (name "unconnected-(U104-VDD_AUX-Pad44)") (class "Default")
      (node (ref "U104") (pin "44") (pinfunction "VDD_AUX_44") (pintype "output"))
    )
    (net (code "241") (name "unconnected-(U105-C4-Pad5)") (class "Default")
      (node (ref "U105") (pin "5") (pinfunction "C4_5") (pintype "passive"))
    )
    (net (code "242") (name "unconnected-(U106-C4-Pad5)") (class "Default")
      (node (ref "U106") (pin "5") (pinfunction "C4_5") (pintype "passive"))
    )
  )
)
